# SM3320-BATT-EV.net
KiCad netlist of a schematic drawn in Altium Designer
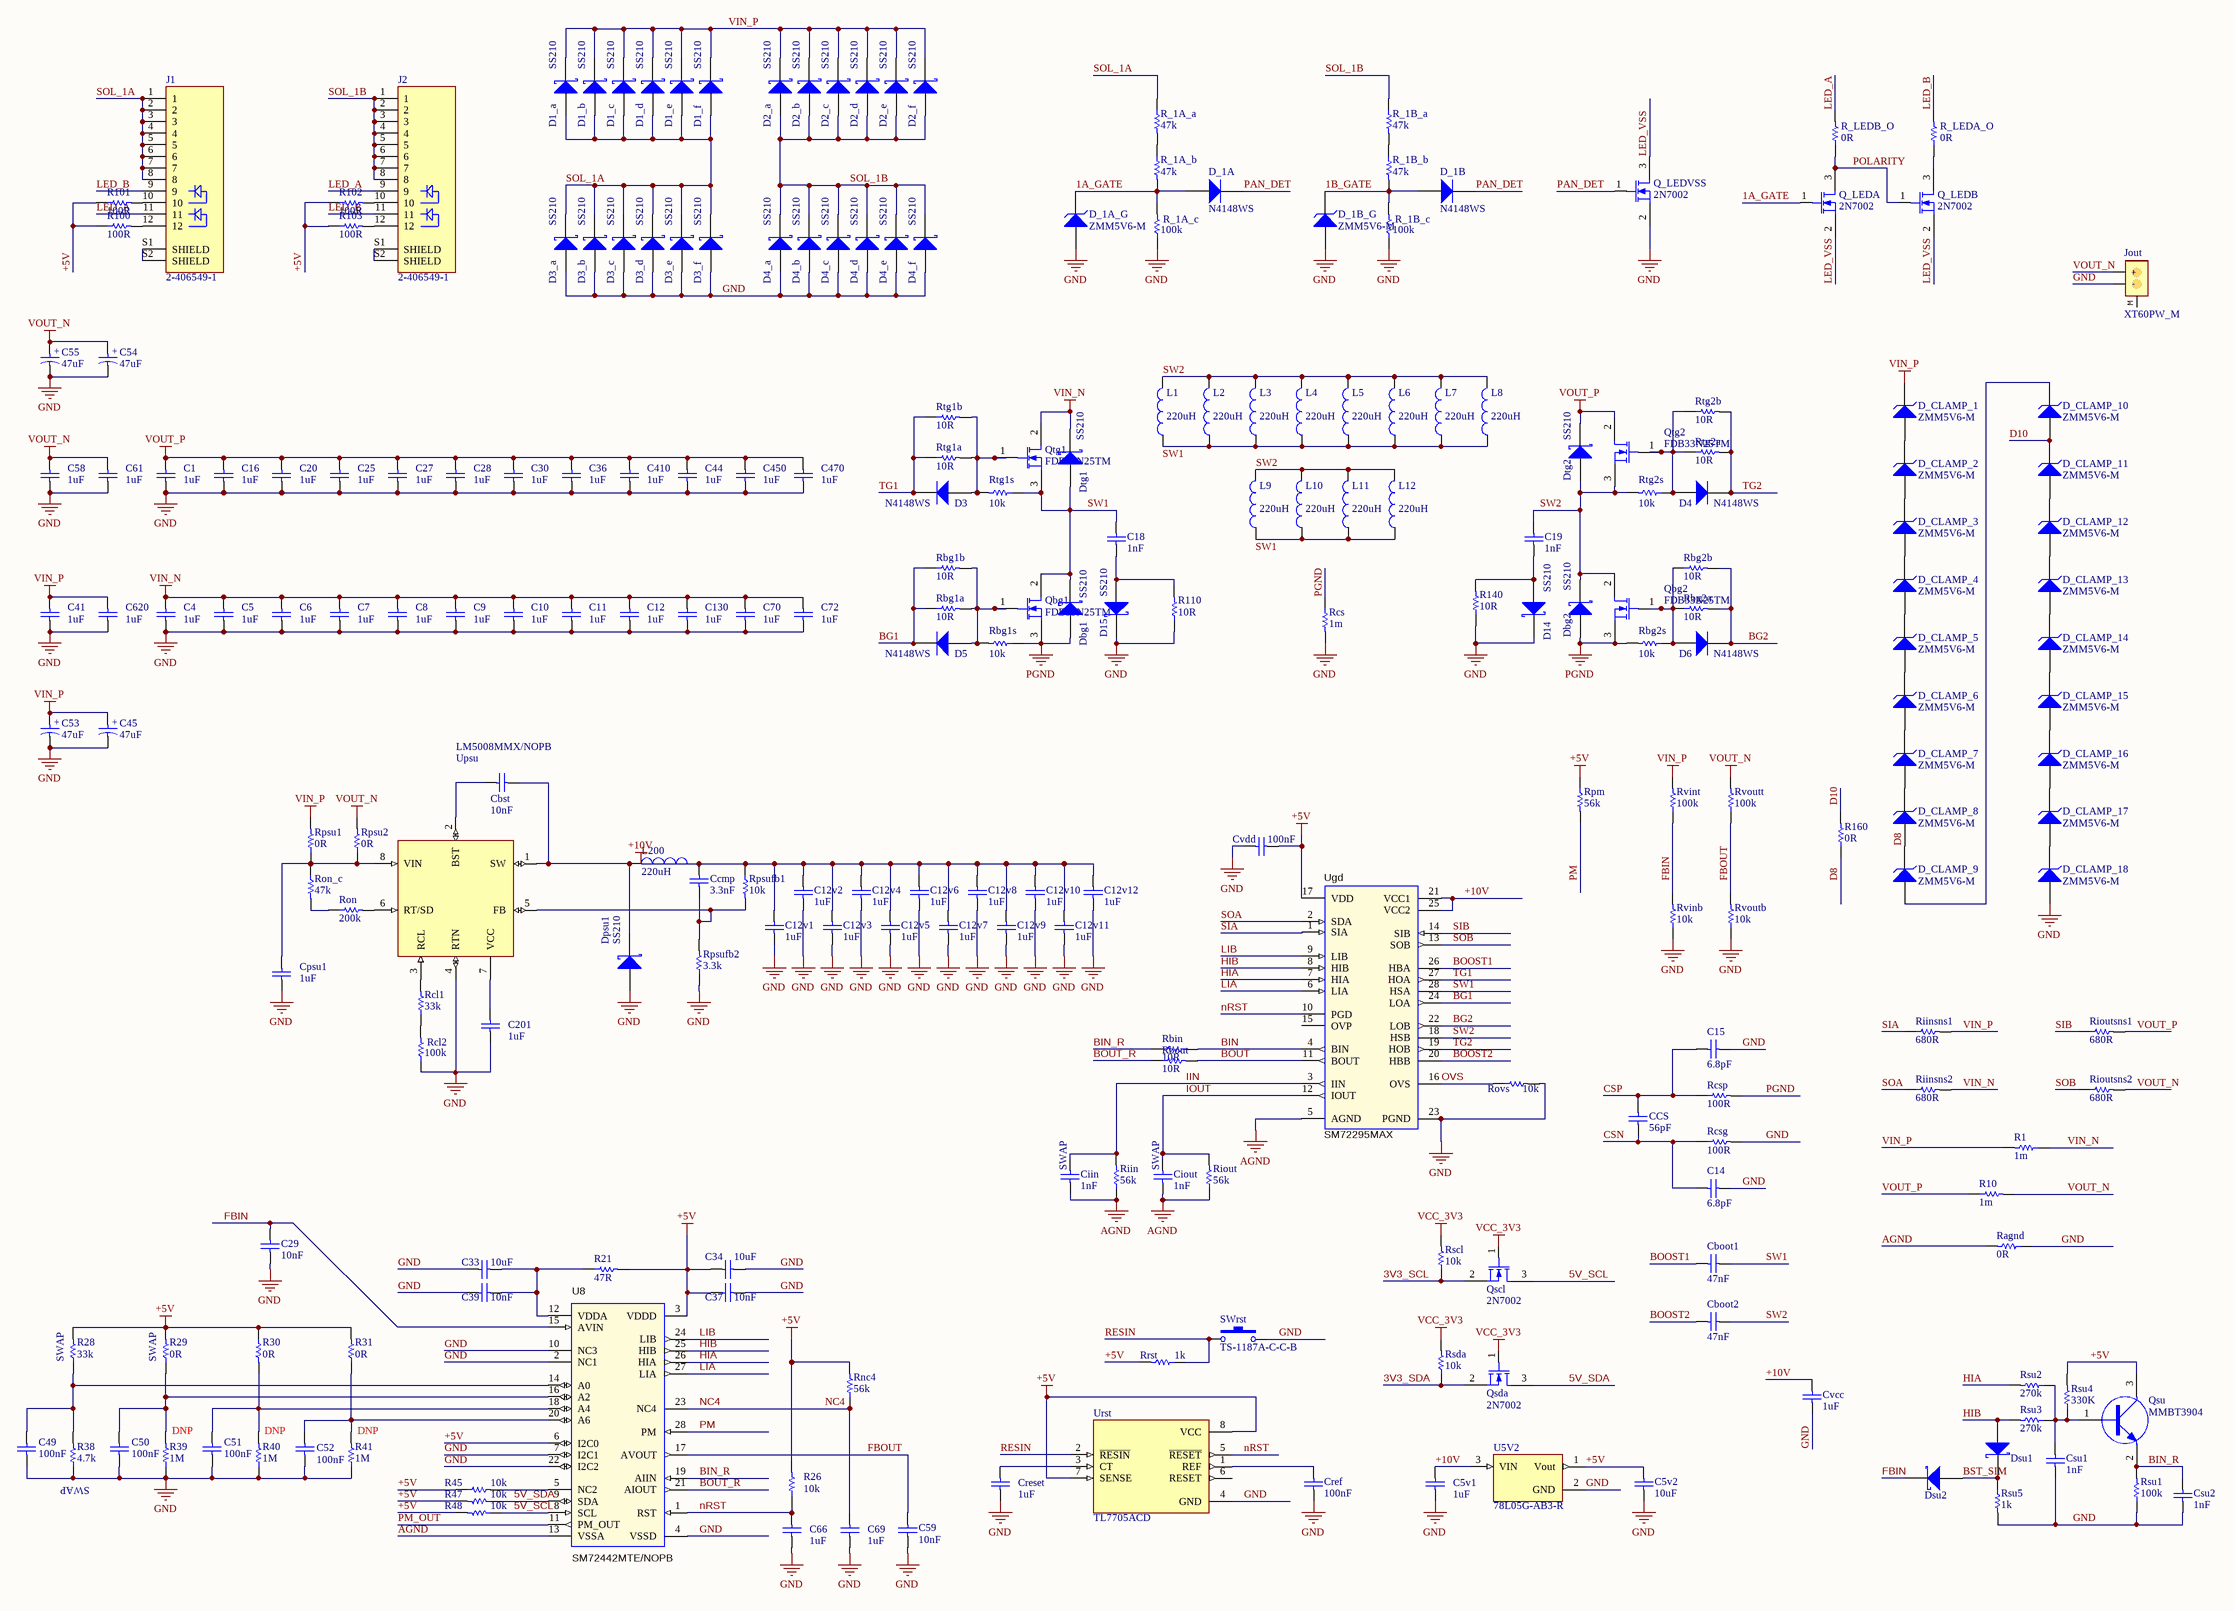
[diagram p0: SM3320-BATT-EV.SchDoc]

(export (version "E")
  (design (tool "Eeschema 10.0.6"))
  (components
    (comp (ref "C1")
      (value "1uF")
      (footprint "C_1206")
      (description "C - CAPACITOR - MLCC - 1uF - 100V - 1206 - X7R")
      (fields (field (name "LCSC PART #") "C91151") (field (name "Comment") "1206B105K101NT"))
      (libsource (lib "JLC_PCB") (part "1206B105K101NT"))
    )
    (comp (ref "C4")
      (value "1uF")
      (footprint "C_1206")
      (description "C - CAPACITOR - MLCC - 1uF - 100V - 1206 - X7R")
      (fields (field (name "LCSC PART #") "C91151") (field (name "Comment") "1206B105K101NT"))
      (libsource (lib "JLC_PCB") (part "1206B105K101NT"))
    )
    (comp (ref "C5")
      (value "1uF")
      (footprint "C_1206")
      (description "C - CAPACITOR - MLCC - 1uF - 100V - 1206 - X7R")
      (fields (field (name "LCSC PART #") "C91151") (field (name "Comment") "1206B105K101NT"))
      (libsource (lib "JLC_PCB") (part "1206B105K101NT"))
    )
    (comp (ref "C5v1")
      (value "1uF")
      (footprint "C_0402")
      (description "C - CAPACITOR - MLCC - 1uF - 25V - 0402")
      (fields (field (name "LCSC PART #") "C52923") (field (name "Comment") "CL05A105KA5NQNC"))
      (libsource (lib "JLC_PCB") (part "CL05A105KA5NQNC"))
    )
    (comp (ref "C5v2")
      (value "10uF")
      (footprint "C_0402")
      (description "C - CAPACITOR - MLCC - 10uF - 6.3V - 0402")
      (fields (field (name "LCSC PART #") "C15525") (field (name "Comment") "CL05A106MQ5NUNC"))
      (libsource (lib "JLC_PCB") (part "CL05A106MQ5NUNC"))
    )
    (comp (ref "C6")
      (value "1uF")
      (footprint "C_1206")
      (description "C - CAPACITOR - MLCC - 1uF - 100V - 1206 - X7R")
      (fields (field (name "LCSC PART #") "C91151") (field (name "Comment") "1206B105K101NT"))
      (libsource (lib "JLC_PCB") (part "1206B105K101NT"))
    )
    (comp (ref "C7")
      (value "1uF")
      (footprint "C_1206")
      (description "C - CAPACITOR - MLCC - 1uF - 100V - 1206 - X7R")
      (fields (field (name "LCSC PART #") "C91151") (field (name "Comment") "1206B105K101NT"))
      (libsource (lib "JLC_PCB") (part "1206B105K101NT"))
    )
    (comp (ref "C8")
      (value "1uF")
      (footprint "C_1206")
      (description "C - CAPACITOR - MLCC - 1uF - 100V - 1206 - X7R")
      (fields (field (name "LCSC PART #") "C91151") (field (name "Comment") "1206B105K101NT"))
      (libsource (lib "JLC_PCB") (part "1206B105K101NT"))
    )
    (comp (ref "C9")
      (value "1uF")
      (footprint "C_1206")
      (description "C - CAPACITOR - MLCC - 1uF - 100V - 1206 - X7R")
      (fields (field (name "LCSC PART #") "C91151") (field (name "Comment") "1206B105K101NT"))
      (libsource (lib "JLC_PCB") (part "1206B105K101NT"))
    )
    (comp (ref "C10")
      (value "1uF")
      (footprint "C_1206")
      (description "C - CAPACITOR - MLCC - 1uF - 100V - 1206 - X7R")
      (fields (field (name "LCSC PART #") "C91151") (field (name "Comment") "1206B105K101NT"))
      (libsource (lib "JLC_PCB") (part "1206B105K101NT"))
    )
    (comp (ref "C11")
      (value "1uF")
      (footprint "C_1206")
      (description "C - CAPACITOR - MLCC - 1uF - 100V - 1206 - X7R")
      (fields (field (name "LCSC PART #") "C91151") (field (name "Comment") "1206B105K101NT"))
      (libsource (lib "JLC_PCB") (part "1206B105K101NT"))
    )
    (comp (ref "C12")
      (value "1uF")
      (footprint "C_1206")
      (description "C - CAPACITOR - MLCC - 1uF - 100V - 1206 - X7R")
      (fields (field (name "LCSC PART #") "C91151") (field (name "Comment") "1206B105K101NT"))
      (libsource (lib "JLC_PCB") (part "1206B105K101NT"))
    )
    (comp (ref "C12v1")
      (value "1uF")
      (footprint "C_0402")
      (description "C - CAPACITOR - MLCC - 1uF - 25V - 0402")
      (fields (field (name "LCSC PART #") "C52923") (field (name "Comment") "CL05A105KA5NQNC"))
      (libsource (lib "JLC_PCB") (part "CL05A105KA5NQNC"))
    )
    (comp (ref "C12v2")
      (value "1uF")
      (footprint "C_0402")
      (description "C - CAPACITOR - MLCC - 1uF - 25V - 0402")
      (fields (field (name "LCSC PART #") "C52923") (field (name "Comment") "CL05A105KA5NQNC"))
      (libsource (lib "JLC_PCB") (part "CL05A105KA5NQNC"))
    )
    (comp (ref "C12v3")
      (value "1uF")
      (footprint "C_0402")
      (description "C - CAPACITOR - MLCC - 1uF - 25V - 0402")
      (fields (field (name "LCSC PART #") "C52923") (field (name "Comment") "CL05A105KA5NQNC"))
      (libsource (lib "JLC_PCB") (part "CL05A105KA5NQNC"))
    )
    (comp (ref "C12v4")
      (value "1uF")
      (footprint "C_0402")
      (description "C - CAPACITOR - MLCC - 1uF - 25V - 0402")
      (fields (field (name "LCSC PART #") "C52923") (field (name "Comment") "CL05A105KA5NQNC"))
      (libsource (lib "JLC_PCB") (part "CL05A105KA5NQNC"))
    )
    (comp (ref "C12v5")
      (value "1uF")
      (footprint "C_0402")
      (description "C - CAPACITOR - MLCC - 1uF - 25V - 0402")
      (fields (field (name "LCSC PART #") "C52923") (field (name "Comment") "CL05A105KA5NQNC"))
      (libsource (lib "JLC_PCB") (part "CL05A105KA5NQNC"))
    )
    (comp (ref "C12v6")
      (value "1uF")
      (footprint "C_0402")
      (description "C - CAPACITOR - MLCC - 1uF - 25V - 0402")
      (fields (field (name "LCSC PART #") "C52923") (field (name "Comment") "CL05A105KA5NQNC"))
      (libsource (lib "JLC_PCB") (part "CL05A105KA5NQNC"))
    )
    (comp (ref "C12v7")
      (value "1uF")
      (footprint "C_0402")
      (description "C - CAPACITOR - MLCC - 1uF - 25V - 0402")
      (fields (field (name "LCSC PART #") "C52923") (field (name "Comment") "CL05A105KA5NQNC"))
      (libsource (lib "JLC_PCB") (part "CL05A105KA5NQNC"))
    )
    (comp (ref "C12v8")
      (value "1uF")
      (footprint "C_0402")
      (description "C - CAPACITOR - MLCC - 1uF - 25V - 0402")
      (fields (field (name "LCSC PART #") "C52923") (field (name "Comment") "CL05A105KA5NQNC"))
      (libsource (lib "JLC_PCB") (part "CL05A105KA5NQNC"))
    )
    (comp (ref "C12v9")
      (value "1uF")
      (footprint "C_0402")
      (description "C - CAPACITOR - MLCC - 1uF - 25V - 0402")
      (fields (field (name "LCSC PART #") "C52923") (field (name "Comment") "CL05A105KA5NQNC"))
      (libsource (lib "JLC_PCB") (part "CL05A105KA5NQNC"))
    )
    (comp (ref "C12v10")
      (value "1uF")
      (footprint "C_0402")
      (description "C - CAPACITOR - MLCC - 1uF - 25V - 0402")
      (fields (field (name "LCSC PART #") "C52923") (field (name "Comment") "CL05A105KA5NQNC"))
      (libsource (lib "JLC_PCB") (part "CL05A105KA5NQNC"))
    )
    (comp (ref "C12v11")
      (value "1uF")
      (footprint "C_0402")
      (description "C - CAPACITOR - MLCC - 1uF - 25V - 0402")
      (fields (field (name "LCSC PART #") "C52923") (field (name "Comment") "CL05A105KA5NQNC"))
      (libsource (lib "JLC_PCB") (part "CL05A105KA5NQNC"))
    )
    (comp (ref "C12v12")
      (value "1uF")
      (footprint "C_0402")
      (description "C - CAPACITOR - MLCC - 1uF - 25V - 0402")
      (fields (field (name "LCSC PART #") "C52923") (field (name "Comment") "CL05A105KA5NQNC"))
      (libsource (lib "JLC_PCB") (part "CL05A105KA5NQNC"))
    )
    (comp (ref "C14")
      (value "6.8pF")
      (footprint "C_0402")
      (description "C - CAPACITOR - MLCC - 6.8pF - 50V - 0402")
      (fields (field (name "LCSC PART #") "C1576") (field (name "Comment") "0402CG6R8C500NT"))
      (libsource (lib "JLC_PCB") (part "0402CG6R8C500NT"))
    )
    (comp (ref "C15")
      (value "6.8pF")
      (footprint "C_0402")
      (description "C - CAPACITOR - MLCC - 6.8pF - 50V - 0402")
      (fields (field (name "LCSC PART #") "C1576") (field (name "Comment") "0402CG6R8C500NT"))
      (libsource (lib "JLC_PCB") (part "0402CG6R8C500NT"))
    )
    (comp (ref "C16")
      (value "1uF")
      (footprint "C_1206")
      (description "C - CAPACITOR - MLCC - 1uF - 100V - 1206 - X7R")
      (fields (field (name "LCSC PART #") "C91151") (field (name "Comment") "1206B105K101NT"))
      (libsource (lib "JLC_PCB") (part "1206B105K101NT"))
    )
    (comp (ref "C18")
      (value "1nF")
      (footprint "C_1206")
      (description "C - CAPACITOR - MLCC - 1nF - 2000V - 1206 - X7R")
      (fields (field (name "LCSC PART #") "C9196") (field (name "Comment") "1206B102K202NT"))
      (libsource (lib "JLC_PCB") (part "1206B102K202NT"))
    )
    (comp (ref "C19")
      (value "1nF")
      (footprint "C_1206")
      (description "C - CAPACITOR - MLCC - 1nF - 2000V - 1206 - X7R")
      (fields (field (name "LCSC PART #") "C9196") (field (name "Comment") "1206B102K202NT"))
      (libsource (lib "JLC_PCB") (part "1206B102K202NT"))
    )
    (comp (ref "C20")
      (value "1uF")
      (footprint "C_1206")
      (description "C - CAPACITOR - MLCC - 1uF - 100V - 1206 - X7R")
      (fields (field (name "LCSC PART #") "C91151") (field (name "Comment") "1206B105K101NT"))
      (libsource (lib "JLC_PCB") (part "1206B105K101NT"))
    )
    (comp (ref "C25")
      (value "1uF")
      (footprint "C_1206")
      (description "C - CAPACITOR - MLCC - 1uF - 100V - 1206 - X7R")
      (fields (field (name "LCSC PART #") "C91151") (field (name "Comment") "1206B105K101NT"))
      (libsource (lib "JLC_PCB") (part "1206B105K101NT"))
    )
    (comp (ref "C27")
      (value "1uF")
      (footprint "C_1206")
      (description "C - CAPACITOR - MLCC - 1uF - 100V - 1206 - X7R")
      (fields (field (name "LCSC PART #") "C91151") (field (name "Comment") "1206B105K101NT"))
      (libsource (lib "JLC_PCB") (part "1206B105K101NT"))
    )
    (comp (ref "C28")
      (value "1uF")
      (footprint "C_1206")
      (description "C - CAPACITOR - MLCC - 1uF - 100V - 1206 - X7R")
      (fields (field (name "LCSC PART #") "C91151") (field (name "Comment") "1206B105K101NT"))
      (libsource (lib "JLC_PCB") (part "1206B105K101NT"))
    )
    (comp (ref "C29")
      (value "10nF")
      (footprint "C_0402")
      (description "C - CAPACITOR - MLCC - 10nF - 50V - 0402")
      (fields (field (name "LCSC PART #") "C15195") (field (name "Comment") "CL05B103KB5NNNC"))
      (libsource (lib "JLC_PCB") (part "CL05B103KB5NNNC"))
    )
    (comp (ref "C30")
      (value "1uF")
      (footprint "C_1206")
      (description "C - CAPACITOR - MLCC - 1uF - 100V - 1206 - X7R")
      (fields (field (name "LCSC PART #") "C91151") (field (name "Comment") "1206B105K101NT"))
      (libsource (lib "JLC_PCB") (part "1206B105K101NT"))
    )
    (comp (ref "C33")
      (value "10uF")
      (footprint "C_0402")
      (description "C - CAPACITOR - MLCC - 10uF - 6.3V - 0402")
      (fields (field (name "LCSC PART #") "C15525") (field (name "Comment") "CL05A106MQ5NUNC"))
      (libsource (lib "JLC_PCB") (part "CL05A106MQ5NUNC"))
    )
    (comp (ref "C34")
      (value "10uF")
      (footprint "C_0402")
      (description "C - CAPACITOR - MLCC - 10uF - 6.3V - 0402")
      (fields (field (name "LCSC PART #") "C15525") (field (name "Comment") "CL05A106MQ5NUNC"))
      (libsource (lib "JLC_PCB") (part "CL05A106MQ5NUNC"))
    )
    (comp (ref "C36")
      (value "1uF")
      (footprint "C_1206")
      (description "C - CAPACITOR - MLCC - 1uF - 100V - 1206 - X7R")
      (fields (field (name "LCSC PART #") "C91151") (field (name "Comment") "1206B105K101NT"))
      (libsource (lib "JLC_PCB") (part "1206B105K101NT"))
    )
    (comp (ref "C37")
      (value "10nF")
      (footprint "C_0402")
      (description "C - CAPACITOR - MLCC - 10nF - 50V - 0402")
      (fields (field (name "LCSC PART #") "C15195") (field (name "Comment") "CL05B103KB5NNNC"))
      (libsource (lib "JLC_PCB") (part "CL05B103KB5NNNC"))
    )
    (comp (ref "C39")
      (value "10nF")
      (footprint "C_0402")
      (description "C - CAPACITOR - MLCC - 10nF - 50V - 0402")
      (fields (field (name "LCSC PART #") "C15195") (field (name "Comment") "CL05B103KB5NNNC"))
      (libsource (lib "JLC_PCB") (part "CL05B103KB5NNNC"))
    )
    (comp (ref "C41")
      (value "1uF")
      (footprint "C_1206")
      (description "C - CAPACITOR - MLCC - 1uF - 100V - 1206 - X7R")
      (fields (field (name "LCSC PART #") "C91151") (field (name "Comment") "1206B105K101NT"))
      (libsource (lib "JLC_PCB") (part "1206B105K101NT"))
    )
    (comp (ref "C44")
      (value "1uF")
      (footprint "C_1206")
      (description "C - CAPACITOR - MLCC - 1uF - 100V - 1206 - X7R")
      (fields (field (name "LCSC PART #") "C91151") (field (name "Comment") "1206B105K101NT"))
      (libsource (lib "JLC_PCB") (part "1206B105K101NT"))
    )
    (comp (ref "C45")
      (value "47uF")
      (footprint "C_CAN_1010")
      (description "C - CAPACITOR - ELECTROLYTIC - 47uF - 100V")
      (fields (field (name "LCSC PART #") "C164068") (field (name "Comment") "VZH470M2ATR-1010"))
      (libsource (lib "JLC_PCB") (part "VZH470M2ATR-1010"))
    )
    (comp (ref "C49")
      (value "100nF")
      (footprint "C_0402")
      (description "C - CAPACITOR - MLCC - 100nF - 16V - 0402")
      (fields (field (name "LCSC PART #") "C1525") (field (name "Comment") "CL05B104KO5NNNC"))
      (libsource (lib "JLC_PCB") (part "CL05B104KO5NNNC"))
    )
    (comp (ref "C50")
      (value "100nF")
      (footprint "C_0402")
      (description "C - CAPACITOR - MLCC - 100nF - 16V - 0402")
      (fields (field (name "LCSC PART #") "C1525") (field (name "Comment") "CL05B104KO5NNNC"))
      (libsource (lib "JLC_PCB") (part "CL05B104KO5NNNC"))
    )
    (comp (ref "C51")
      (value "100nF")
      (footprint "C_0402")
      (description "C - CAPACITOR - MLCC - 100nF - 16V - 0402")
      (fields (field (name "LCSC PART #") "C1525") (field (name "Comment") "CL05B104KO5NNNC"))
      (libsource (lib "JLC_PCB") (part "CL05B104KO5NNNC"))
    )
    (comp (ref "C52")
      (value "100nF")
      (footprint "C_0402")
      (description "C - CAPACITOR - MLCC - 100nF - 16V - 0402")
      (fields (field (name "LCSC PART #") "C1525") (field (name "Comment") "CL05B104KO5NNNC"))
      (libsource (lib "JLC_PCB") (part "CL05B104KO5NNNC"))
    )
    (comp (ref "C53")
      (value "47uF")
      (footprint "C_CAN_1010")
      (description "C - CAPACITOR - ELECTROLYTIC - 47uF - 100V")
      (fields (field (name "LCSC PART #") "C164068") (field (name "Comment") "VZH470M2ATR-1010"))
      (libsource (lib "JLC_PCB") (part "VZH470M2ATR-1010"))
    )
    (comp (ref "C54")
      (value "47uF")
      (footprint "C_CAN_1010")
      (description "C - CAPACITOR - ELECTROLYTIC - 47uF - 100V")
      (fields (field (name "LCSC PART #") "C164068") (field (name "Comment") "VZH470M2ATR-1010"))
      (libsource (lib "JLC_PCB") (part "VZH470M2ATR-1010"))
    )
    (comp (ref "C55")
      (value "47uF")
      (footprint "C_CAN_1010")
      (description "C - CAPACITOR - ELECTROLYTIC - 47uF - 100V")
      (fields (field (name "LCSC PART #") "C164068") (field (name "Comment") "VZH470M2ATR-1010"))
      (libsource (lib "JLC_PCB") (part "VZH470M2ATR-1010"))
    )
    (comp (ref "C58")
      (value "1uF")
      (footprint "C_1206")
      (description "C - CAPACITOR - MLCC - 1uF - 100V - 1206 - X7R")
      (fields (field (name "LCSC PART #") "C91151") (field (name "Comment") "1206B105K101NT"))
      (libsource (lib "JLC_PCB") (part "1206B105K101NT"))
    )
    (comp (ref "C59")
      (value "10nF")
      (footprint "C_0402")
      (description "C - CAPACITOR - MLCC - 10nF - 50V - 0402")
      (fields (field (name "LCSC PART #") "C15195") (field (name "Comment") "CL05B103KB5NNNC"))
      (libsource (lib "JLC_PCB") (part "CL05B103KB5NNNC"))
    )
    (comp (ref "C61")
      (value "1uF")
      (footprint "C_1206")
      (description "C - CAPACITOR - MLCC - 1uF - 100V - 1206 - X7R")
      (fields (field (name "LCSC PART #") "C91151") (field (name "Comment") "1206B105K101NT"))
      (libsource (lib "JLC_PCB") (part "1206B105K101NT"))
    )
    (comp (ref "C66")
      (value "1uF")
      (footprint "C_0402")
      (description "C - CAPACITOR - MLCC - 1uF - 25V - 0402")
      (fields (field (name "LCSC PART #") "C52923") (field (name "Comment") "CL05A105KA5NQNC"))
      (libsource (lib "JLC_PCB") (part "CL05A105KA5NQNC"))
    )
    (comp (ref "C69")
      (value "1uF")
      (footprint "C_0402")
      (description "C - CAPACITOR - MLCC - 1uF - 25V - 0402")
      (fields (field (name "LCSC PART #") "C52923") (field (name "Comment") "CL05A105KA5NQNC"))
      (libsource (lib "JLC_PCB") (part "CL05A105KA5NQNC"))
    )
    (comp (ref "C70")
      (value "1uF")
      (footprint "C_1206")
      (description "C - CAPACITOR - MLCC - 1uF - 100V - 1206 - X7R")
      (fields (field (name "LCSC PART #") "C91151") (field (name "Comment") "1206B105K101NT"))
      (libsource (lib "JLC_PCB") (part "1206B105K101NT"))
    )
    (comp (ref "C72")
      (value "1uF")
      (footprint "C_1206")
      (description "C - CAPACITOR - MLCC - 1uF - 100V - 1206 - X7R")
      (fields (field (name "LCSC PART #") "C91151") (field (name "Comment") "1206B105K101NT"))
      (libsource (lib "JLC_PCB") (part "1206B105K101NT"))
    )
    (comp (ref "C130")
      (value "1uF")
      (footprint "C_1206")
      (description "C - CAPACITOR - MLCC - 1uF - 100V - 1206 - X7R")
      (fields (field (name "LCSC PART #") "C91151") (field (name "Comment") "1206B105K101NT"))
      (libsource (lib "JLC_PCB") (part "1206B105K101NT"))
    )
    (comp (ref "C201")
      (value "1uF")
      (footprint "C_0402")
      (description "C - CAPACITOR - MLCC - 1uF - 25V - 0402")
      (fields (field (name "LCSC PART #") "C52923") (field (name "Comment") "CL05A105KA5NQNC"))
      (libsource (lib "JLC_PCB") (part "CL05A105KA5NQNC"))
    )
    (comp (ref "C410")
      (value "1uF")
      (footprint "C_1206")
      (description "C - CAPACITOR - MLCC - 1uF - 100V - 1206 - X7R")
      (fields (field (name "LCSC PART #") "C91151") (field (name "Comment") "1206B105K101NT"))
      (libsource (lib "JLC_PCB") (part "1206B105K101NT"))
    )
    (comp (ref "C450")
      (value "1uF")
      (footprint "C_1206")
      (description "C - CAPACITOR - MLCC - 1uF - 100V - 1206 - X7R")
      (fields (field (name "LCSC PART #") "C91151") (field (name "Comment") "1206B105K101NT"))
      (libsource (lib "JLC_PCB") (part "1206B105K101NT"))
    )
    (comp (ref "C470")
      (value "1uF")
      (footprint "C_1206")
      (description "C - CAPACITOR - MLCC - 1uF - 100V - 1206 - X7R")
      (fields (field (name "LCSC PART #") "C91151") (field (name "Comment") "1206B105K101NT"))
      (libsource (lib "JLC_PCB") (part "1206B105K101NT"))
    )
    (comp (ref "C620")
      (value "1uF")
      (footprint "C_1206")
      (description "C - CAPACITOR - MLCC - 1uF - 100V - 1206 - X7R")
      (fields (field (name "LCSC PART #") "C91151") (field (name "Comment") "1206B105K101NT"))
      (libsource (lib "JLC_PCB") (part "1206B105K101NT"))
    )
    (comp (ref "Cboot1")
      (value "47nF")
      (footprint "C_0603")
      (description "C - CAPACITOR - MLCC - 470nF - 25V - 0603")
      (fields (field (name "LCSC PART #") "C1623") (field (name "Comment") "CL10B474KA8NNNC"))
      (libsource (lib "JLC_PCB") (part "CL10B474KA8NNNC"))
    )
    (comp (ref "Cboot2")
      (value "47nF")
      (footprint "C_0603")
      (description "C - CAPACITOR - MLCC - 470nF - 25V - 0603")
      (fields (field (name "LCSC PART #") "C1623") (field (name "Comment") "CL10B474KA8NNNC"))
      (libsource (lib "JLC_PCB") (part "CL10B474KA8NNNC"))
    )
    (comp (ref "Cbst")
      (value "10nF")
      (footprint "C_0402")
      (description "C - CAPACITOR - MLCC - 10nF - 50V - 0402")
      (fields (field (name "LCSC PART #") "C15195") (field (name "Comment") "CL05B103KB5NNNC"))
      (libsource (lib "JLC_PCB") (part "CL05B103KB5NNNC"))
    )
    (comp (ref "Ccmp")
      (value "3.3nF")
      (footprint "C_0402")
      (description "C - CAPACITOR - MLCC - 3.3nF - 50V - 0402")
      (fields (field (name "LCSC PART #") "C26404") (field (name "Comment") "CL05B332KB5NNNC"))
      (libsource (lib "JLC_PCB") (part "CL05B332KB5NNNC"))
    )
    (comp (ref "CCS")
      (value "56pF")
      (footprint "C_0402")
      (description "C - CAPACITOR - MLCC - 56pF - 50V -  0402")
      (fields (field (name "LCSC PART #") "C1572") (field (name "Comment") "0402CG560J500NT"))
      (libsource (lib "JLC_PCB") (part "0402CG560J500NT"))
    )
    (comp (ref "Ciin")
      (value "1nF")
      (footprint "C_0402")
      (description "C - CAPACITOR - MLCC - 1nF - 50V - 0402")
      (fields (field (name "LCSC PART #") "C1523") (field (name "Comment") "0402B102K500NT"))
      (libsource (lib "JLC_PCB") (part "0402B102K500NT"))
    )
    (comp (ref "Ciout")
      (value "1nF")
      (footprint "C_0402")
      (description "C - CAPACITOR - MLCC - 1nF - 50V - 0402")
      (fields (field (name "LCSC PART #") "C1523") (field (name "Comment") "0402B102K500NT"))
      (libsource (lib "JLC_PCB") (part "0402B102K500NT"))
    )
    (comp (ref "Cpsu1")
      (value "1uF")
      (footprint "C_1206")
      (description "C - CAPACITOR - MLCC - 1uF - 100V - 1206 - X7R")
      (fields (field (name "LCSC PART #") "C91151") (field (name "Comment") "1206B105K101NT"))
      (libsource (lib "JLC_PCB") (part "1206B105K101NT"))
    )
    (comp (ref "Cref")
      (value "100nF")
      (footprint "C_0402")
      (description "C - CAPACITOR - MLCC - 100nF - 16V - 0402")
      (fields (field (name "LCSC PART #") "C1525") (field (name "Comment") "CL05B104KO5NNNC"))
      (libsource (lib "JLC_PCB") (part "CL05B104KO5NNNC"))
    )
    (comp (ref "Creset")
      (value "1uF")
      (footprint "C_0402")
      (description "C - CAPACITOR - MLCC - 1uF - 25V - 0402")
      (fields (field (name "LCSC PART #") "C52923") (field (name "Comment") "CL05A105KA5NQNC"))
      (libsource (lib "JLC_PCB") (part "CL05A105KA5NQNC"))
    )
    (comp (ref "Csu1")
      (value "1nF")
      (footprint "C_0402")
      (description "C - CAPACITOR - MLCC - 1nF - 50V - 0402")
      (fields (field (name "LCSC PART #") "C1523") (field (name "Comment") "0402B102K500NT"))
      (libsource (lib "JLC_PCB") (part "0402B102K500NT"))
    )
    (comp (ref "Csu2")
      (value "1nF")
      (footprint "C_0402")
      (description "C - CAPACITOR - MLCC - 1nF - 50V - 0402")
      (fields (field (name "LCSC PART #") "C1523") (field (name "Comment") "0402B102K500NT"))
      (libsource (lib "JLC_PCB") (part "0402B102K500NT"))
    )
    (comp (ref "Cvcc")
      (value "1uF")
      (footprint "C_0402")
      (description "C - CAPACITOR - MLCC - 1uF - 25V - 0402")
      (fields (field (name "LCSC PART #") "C52923") (field (name "Comment") "CL05A105KA5NQNC"))
      (libsource (lib "JLC_PCB") (part "CL05A105KA5NQNC"))
    )
    (comp (ref "Cvdd")
      (value "100nF")
      (footprint "C_0402")
      (description "C - CAPACITOR - MLCC - 100nF - 16V - 0402")
      (fields (field (name "LCSC PART #") "C1525") (field (name "Comment") "CL05B104KO5NNNC"))
      (libsource (lib "JLC_PCB") (part "CL05B104KO5NNNC"))
    )
    (comp (ref "D1_a")
      (value "SS210")
      (footprint "DO-214AC")
      (description "D - DIODE - SCHOTTKY - 100V - 2A")
      (fields (field (name "LCSC PART #") "C14996"))
      (libsource (lib "JLC_PCB") (part "SS210"))
    )
    (comp (ref "D1_b")
      (value "SS210")
      (footprint "DO-214AC")
      (description "D - DIODE - SCHOTTKY - 100V - 2A")
      (fields (field (name "LCSC PART #") "C14996"))
      (libsource (lib "JLC_PCB") (part "SS210"))
    )
    (comp (ref "D1_c")
      (value "SS210")
      (footprint "DO-214AC")
      (description "D - DIODE - SCHOTTKY - 100V - 2A")
      (fields (field (name "LCSC PART #") "C14996"))
      (libsource (lib "JLC_PCB") (part "SS210"))
    )
    (comp (ref "D1_d")
      (value "SS210")
      (footprint "DO-214AC")
      (description "D - DIODE - SCHOTTKY - 100V - 2A")
      (fields (field (name "LCSC PART #") "C14996"))
      (libsource (lib "JLC_PCB") (part "SS210"))
    )
    (comp (ref "D1_e")
      (value "SS210")
      (footprint "DO-214AC")
      (description "D - DIODE - SCHOTTKY - 100V - 2A")
      (fields (field (name "LCSC PART #") "C14996"))
      (libsource (lib "JLC_PCB") (part "SS210"))
    )
    (comp (ref "D1_f")
      (value "SS210")
      (footprint "DO-214AC")
      (description "D - DIODE - SCHOTTKY - 100V - 2A")
      (fields (field (name "LCSC PART #") "C14996"))
      (libsource (lib "JLC_PCB") (part "SS210"))
    )
    (comp (ref "D2_a")
      (value "SS210")
      (footprint "DO-214AC")
      (description "D - DIODE - SCHOTTKY - 100V - 2A")
      (fields (field (name "LCSC PART #") "C14996"))
      (libsource (lib "JLC_PCB") (part "SS210"))
    )
    (comp (ref "D2_b")
      (value "SS210")
      (footprint "DO-214AC")
      (description "D - DIODE - SCHOTTKY - 100V - 2A")
      (fields (field (name "LCSC PART #") "C14996"))
      (libsource (lib "JLC_PCB") (part "SS210"))
    )
    (comp (ref "D2_c")
      (value "SS210")
      (footprint "DO-214AC")
      (description "D - DIODE - SCHOTTKY - 100V - 2A")
      (fields (field (name "LCSC PART #") "C14996"))
      (libsource (lib "JLC_PCB") (part "SS210"))
    )
    (comp (ref "D2_d")
      (value "SS210")
      (footprint "DO-214AC")
      (description "D - DIODE - SCHOTTKY - 100V - 2A")
      (fields (field (name "LCSC PART #") "C14996"))
      (libsource (lib "JLC_PCB") (part "SS210"))
    )
    (comp (ref "D2_e")
      (value "SS210")
      (footprint "DO-214AC")
      (description "D - DIODE - SCHOTTKY - 100V - 2A")
      (fields (field (name "LCSC PART #") "C14996"))
      (libsource (lib "JLC_PCB") (part "SS210"))
    )
    (comp (ref "D2_f")
      (value "SS210")
      (footprint "DO-214AC")
      (description "D - DIODE - SCHOTTKY - 100V - 2A")
      (fields (field (name "LCSC PART #") "C14996"))
      (libsource (lib "JLC_PCB") (part "SS210"))
    )
    (comp (ref "D3")
      (value "N4148WS")
      (footprint "SOD-323")
      (description "D - DIODE - FAST TRR - 100V - 150mA - 4ns")
      (fields (field (name "LCSC PART #") "C2128"))
      (libsource (lib "JLC_PCB") (part "N4148WS"))
    )
    (comp (ref "D3_a")
      (value "SS210")
      (footprint "DO-214AC")
      (description "D - DIODE - SCHOTTKY - 100V - 2A")
      (fields (field (name "LCSC PART #") "C14996"))
      (libsource (lib "JLC_PCB") (part "SS210"))
    )
    (comp (ref "D3_b")
      (value "SS210")
      (footprint "DO-214AC")
      (description "D - DIODE - SCHOTTKY - 100V - 2A")
      (fields (field (name "LCSC PART #") "C14996"))
      (libsource (lib "JLC_PCB") (part "SS210"))
    )
    (comp (ref "D3_c")
      (value "SS210")
      (footprint "DO-214AC")
      (description "D - DIODE - SCHOTTKY - 100V - 2A")
      (fields (field (name "LCSC PART #") "C14996"))
      (libsource (lib "JLC_PCB") (part "SS210"))
    )
    (comp (ref "D3_d")
      (value "SS210")
      (footprint "DO-214AC")
      (description "D - DIODE - SCHOTTKY - 100V - 2A")
      (fields (field (name "LCSC PART #") "C14996"))
      (libsource (lib "JLC_PCB") (part "SS210"))
    )
    (comp (ref "D3_e")
      (value "SS210")
      (footprint "DO-214AC")
      (description "D - DIODE - SCHOTTKY - 100V - 2A")
      (fields (field (name "LCSC PART #") "C14996"))
      (libsource (lib "JLC_PCB") (part "SS210"))
    )
    (comp (ref "D3_f")
      (value "SS210")
      (footprint "DO-214AC")
      (description "D - DIODE - SCHOTTKY - 100V - 2A")
      (fields (field (name "LCSC PART #") "C14996"))
      (libsource (lib "JLC_PCB") (part "SS210"))
    )
    (comp (ref "D4")
      (value "N4148WS")
      (footprint "SOD-323")
      (description "D - DIODE - FAST TRR - 100V - 150mA - 4ns")
      (fields (field (name "LCSC PART #") "C2128"))
      (libsource (lib "JLC_PCB") (part "N4148WS"))
    )
    (comp (ref "D4_a")
      (value "SS210")
      (footprint "DO-214AC")
      (description "D - DIODE - SCHOTTKY - 100V - 2A")
      (fields (field (name "LCSC PART #") "C14996"))
      (libsource (lib "JLC_PCB") (part "SS210"))
    )
    (comp (ref "D4_b")
      (value "SS210")
      (footprint "DO-214AC")
      (description "D - DIODE - SCHOTTKY - 100V - 2A")
      (fields (field (name "LCSC PART #") "C14996"))
      (libsource (lib "JLC_PCB") (part "SS210"))
    )
    (comp (ref "D4_c")
      (value "SS210")
      (footprint "DO-214AC")
      (description "D - DIODE - SCHOTTKY - 100V - 2A")
      (fields (field (name "LCSC PART #") "C14996"))
      (libsource (lib "JLC_PCB") (part "SS210"))
    )
    (comp (ref "D4_d")
      (value "SS210")
      (footprint "DO-214AC")
      (description "D - DIODE - SCHOTTKY - 100V - 2A")
      (fields (field (name "LCSC PART #") "C14996"))
      (libsource (lib "JLC_PCB") (part "SS210"))
    )
    (comp (ref "D4_e")
      (value "SS210")
      (footprint "DO-214AC")
      (description "D - DIODE - SCHOTTKY - 100V - 2A")
      (fields (field (name "LCSC PART #") "C14996"))
      (libsource (lib "JLC_PCB") (part "SS210"))
    )
    (comp (ref "D4_f")
      (value "SS210")
      (footprint "DO-214AC")
      (description "D - DIODE - SCHOTTKY - 100V - 2A")
      (fields (field (name "LCSC PART #") "C14996"))
      (libsource (lib "JLC_PCB") (part "SS210"))
    )
    (comp (ref "D5")
      (value "N4148WS")
      (footprint "SOD-323")
      (description "D - DIODE - FAST TRR - 100V - 150mA - 4ns")
      (fields (field (name "LCSC PART #") "C2128"))
      (libsource (lib "JLC_PCB") (part "N4148WS"))
    )
    (comp (ref "D6")
      (value "N4148WS")
      (footprint "SOD-323")
      (description "D - DIODE - FAST TRR - 100V - 150mA - 4ns")
      (fields (field (name "LCSC PART #") "C2128"))
      (libsource (lib "JLC_PCB") (part "N4148WS"))
    )
    (comp (ref "D14")
      (value "SS210")
      (footprint "DO-214AC")
      (description "D - DIODE - SCHOTTKY - 100V - 2A")
      (fields (field (name "LCSC PART #") "C14996"))
      (libsource (lib "JLC_PCB") (part "SS210"))
    )
    (comp (ref "D15")
      (value "SS210")
      (footprint "DO-214AC")
      (description "D - DIODE - SCHOTTKY - 100V - 2A")
      (fields (field (name "LCSC PART #") "C14996"))
      (libsource (lib "JLC_PCB") (part "SS210"))
    )
    (comp (ref "Dbg1")
      (value "SS210")
      (footprint "DO-214AC")
      (description "D - DIODE - SCHOTTKY - 100V - 2A")
      (fields (field (name "LCSC PART #") "C14996"))
      (libsource (lib "JLC_PCB") (part "SS210"))
    )
    (comp (ref "Dbg2")
      (value "SS210")
      (footprint "DO-214AC")
      (description "D - DIODE - SCHOTTKY - 100V - 2A")
      (fields (field (name "LCSC PART #") "C14996"))
      (libsource (lib "JLC_PCB") (part "SS210"))
    )
    (comp (ref "Dpsu1")
      (value "SS210")
      (footprint "DO-214AC")
      (description "D - DIODE - SCHOTTKY - 100V - 2A")
      (fields (field (name "LCSC PART #") "C14996"))
      (libsource (lib "JLC_PCB") (part "SS210"))
    )
    (comp (ref "Dsu1")
      (value "1N5819WS")
      (footprint "SOD-323")
      (description "D - DIODE - SCHOTTKY - 40V - 1A")
      (fields (field (name "LCSC PART #") "C191023"))
      (libsource (lib "JLC_PCB") (part "1N5819WS"))
    )
    (comp (ref "Dsu2")
      (value "1N5819WS")
      (footprint "SOD-323")
      (description "D - DIODE - SCHOTTKY - 40V - 1A")
      (fields (field (name "LCSC PART #") "C191023"))
      (libsource (lib "JLC_PCB") (part "1N5819WS"))
    )
    (comp (ref "Dtg1")
      (value "SS210")
      (footprint "DO-214AC")
      (description "D - DIODE - SCHOTTKY - 100V - 2A")
      (fields (field (name "LCSC PART #") "C14996"))
      (libsource (lib "JLC_PCB") (part "SS210"))
    )
    (comp (ref "Dtg2")
      (value "SS210")
      (footprint "DO-214AC")
      (description "D - DIODE - SCHOTTKY - 100V - 2A")
      (fields (field (name "LCSC PART #") "C14996"))
      (libsource (lib "JLC_PCB") (part "SS210"))
    )
    (comp (ref "D_1A")
      (value "N4148WS")
      (footprint "SOD-323")
      (description "D - DIODE - FAST TRR - 100V - 150mA - 4ns")
      (fields (field (name "LCSC PART #") "C2128"))
      (libsource (lib "JLC_PCB") (part "N4148WS"))
    )
    (comp (ref "D_1A_G")
      (value "ZMM5V6-M")
      (footprint "DO-213AA")
      (description "D - DIODE - ZENER - 5.6V - 500mW")
      (fields (field (name "LCSC PART #") "C8062"))
      (libsource (lib "JLC_PCB") (part "ZMM5V6-M"))
    )
    (comp (ref "D_1B")
      (value "N4148WS")
      (footprint "SOD-323")
      (description "D - DIODE - FAST TRR - 100V - 150mA - 4ns")
      (fields (field (name "LCSC PART #") "C2128"))
      (libsource (lib "JLC_PCB") (part "N4148WS"))
    )
    (comp (ref "D_1B_G")
      (value "ZMM5V6-M")
      (footprint "DO-213AA")
      (description "D - DIODE - ZENER - 5.6V - 500mW")
      (fields (field (name "LCSC PART #") "C8062"))
      (libsource (lib "JLC_PCB") (part "ZMM5V6-M"))
    )
    (comp (ref "D_CLAMP_1")
      (value "ZMM5V6-M")
      (footprint "DO-213AA")
      (description "D - DIODE - ZENER - 5.6V - 500mW")
      (fields (field (name "LCSC PART #") "C8062"))
      (libsource (lib "JLC_PCB") (part "ZMM5V6-M"))
    )
    (comp (ref "D_CLAMP_2")
      (value "ZMM5V6-M")
      (footprint "DO-213AA")
      (description "D - DIODE - ZENER - 5.6V - 500mW")
      (fields (field (name "LCSC PART #") "C8062"))
      (libsource (lib "JLC_PCB") (part "ZMM5V6-M"))
    )
    (comp (ref "D_CLAMP_3")
      (value "ZMM5V6-M")
      (footprint "DO-213AA")
      (description "D - DIODE - ZENER - 5.6V - 500mW")
      (fields (field (name "LCSC PART #") "C8062"))
      (libsource (lib "JLC_PCB") (part "ZMM5V6-M"))
    )
    (comp (ref "D_CLAMP_4")
      (value "ZMM5V6-M")
      (footprint "DO-213AA")
      (description "D - DIODE - ZENER - 5.6V - 500mW")
      (fields (field (name "LCSC PART #") "C8062"))
      (libsource (lib "JLC_PCB") (part "ZMM5V6-M"))
    )
    (comp (ref "D_CLAMP_5")
      (value "ZMM5V6-M")
      (footprint "DO-213AA")
      (description "D - DIODE - ZENER - 5.6V - 500mW")
      (fields (field (name "LCSC PART #") "C8062"))
      (libsource (lib "JLC_PCB") (part "ZMM5V6-M"))
    )
    (comp (ref "D_CLAMP_6")
      (value "ZMM5V6-M")
      (footprint "DO-213AA")
      (description "D - DIODE - ZENER - 5.6V - 500mW")
      (fields (field (name "LCSC PART #") "C8062"))
      (libsource (lib "JLC_PCB") (part "ZMM5V6-M"))
    )
    (comp (ref "D_CLAMP_7")
      (value "ZMM5V6-M")
      (footprint "DO-213AA")
      (description "D - DIODE - ZENER - 5.6V - 500mW")
      (fields (field (name "LCSC PART #") "C8062"))
      (libsource (lib "JLC_PCB") (part "ZMM5V6-M"))
    )
    (comp (ref "D_CLAMP_8")
      (value "ZMM5V6-M")
      (footprint "DO-213AA")
      (description "D - DIODE - ZENER - 5.6V - 500mW")
      (fields (field (name "LCSC PART #") "C8062"))
      (libsource (lib "JLC_PCB") (part "ZMM5V6-M"))
    )
    (comp (ref "D_CLAMP_9")
      (value "ZMM5V6-M")
      (footprint "DO-213AA")
      (description "D - DIODE - ZENER - 5.6V - 500mW")
      (fields (field (name "LCSC PART #") "C8062"))
      (libsource (lib "JLC_PCB") (part "ZMM5V6-M"))
    )
    (comp (ref "D_CLAMP_10")
      (value "ZMM5V6-M")
      (footprint "DO-213AA")
      (description "D - DIODE - ZENER - 5.6V - 500mW")
      (fields (field (name "LCSC PART #") "C8062"))
      (libsource (lib "JLC_PCB") (part "ZMM5V6-M"))
    )
    (comp (ref "D_CLAMP_11")
      (value "ZMM5V6-M")
      (footprint "DO-213AA")
      (description "D - DIODE - ZENER - 5.6V - 500mW")
      (fields (field (name "LCSC PART #") "C8062"))
      (libsource (lib "JLC_PCB") (part "ZMM5V6-M"))
    )
    (comp (ref "D_CLAMP_12")
      (value "ZMM5V6-M")
      (footprint "DO-213AA")
      (description "D - DIODE - ZENER - 5.6V - 500mW")
      (fields (field (name "LCSC PART #") "C8062"))
      (libsource (lib "JLC_PCB") (part "ZMM5V6-M"))
    )
    (comp (ref "D_CLAMP_13")
      (value "ZMM5V6-M")
      (footprint "DO-213AA")
      (description "D - DIODE - ZENER - 5.6V - 500mW")
      (fields (field (name "LCSC PART #") "C8062"))
      (libsource (lib "JLC_PCB") (part "ZMM5V6-M"))
    )
    (comp (ref "D_CLAMP_14")
      (value "ZMM5V6-M")
      (footprint "DO-213AA")
      (description "D - DIODE - ZENER - 5.6V - 500mW")
      (fields (field (name "LCSC PART #") "C8062"))
      (libsource (lib "JLC_PCB") (part "ZMM5V6-M"))
    )
    (comp (ref "D_CLAMP_15")
      (value "ZMM5V6-M")
      (footprint "DO-213AA")
      (description "D - DIODE - ZENER - 5.6V - 500mW")
      (fields (field (name "LCSC PART #") "C8062"))
      (libsource (lib "JLC_PCB") (part "ZMM5V6-M"))
    )
    (comp (ref "D_CLAMP_16")
      (value "ZMM5V6-M")
      (footprint "DO-213AA")
      (description "D - DIODE - ZENER - 5.6V - 500mW")
      (fields (field (name "LCSC PART #") "C8062"))
      (libsource (lib "JLC_PCB") (part "ZMM5V6-M"))
    )
    (comp (ref "D_CLAMP_17")
      (value "ZMM5V6-M")
      (footprint "DO-213AA")
      (description "D - DIODE - ZENER - 5.6V - 500mW")
      (fields (field (name "LCSC PART #") "C8062"))
      (libsource (lib "JLC_PCB") (part "ZMM5V6-M"))
    )
    (comp (ref "D_CLAMP_18")
      (value "ZMM5V6-M")
      (footprint "DO-213AA")
      (description "D - DIODE - ZENER - 5.6V - 500mW")
      (fields (field (name "LCSC PART #") "C8062"))
      (libsource (lib "JLC_PCB") (part "ZMM5V6-M"))
    )
    (comp (ref "J1")
      (value "2-406549-1")
      (footprint "TE_2-406549-1")
      (description "J - JACK - ETHERNET - Right - THT")
      (fields (field (name "LCSC PART #") "C125068"))
      (libsource (lib "JLC_PCB") (part "2-406549-1"))
    )
    (comp (ref "J2")
      (value "2-406549-1")
      (footprint "TE_2-406549-1")
      (description "J - JACK - ETHERNET - Right - THT")
      (fields (field (name "LCSC PART #") "C125068"))
      (libsource (lib "JLC_PCB") (part "2-406549-1"))
    )
    (comp (ref "Jout")
      (value "XT60PW_M")
      (footprint "XT60PW_M")
      (description "J - JACK - POWER - XT60 - RIGHT - MALE")
      (fields (field (name "LCSC PART #") "X"))
      (libsource (lib "JLC_PCB") (part "XT60PW_M"))
    )
    (comp (ref "L1")
      (value "220uH")
      (footprint "SRR1260")
      (description "L - INDUCTOR - 220uH - 1.6A - 12.5mm")
      (fields (field (name "LCSC PART #") "C169380") (field (name "Comment") "SWRB1207S-221MT"))
      (libsource (lib "JLC_PCB") (part "SWRB1207S-221MT"))
    )
    (comp (ref "L2")
      (value "220uH")
      (footprint "SRR1260")
      (description "L - INDUCTOR - 220uH - 1.6A - 12.5mm")
      (fields (field (name "LCSC PART #") "C169380") (field (name "Comment") "SWRB1207S-221MT"))
      (libsource (lib "JLC_PCB") (part "SWRB1207S-221MT"))
    )
    (comp (ref "L3")
      (value "220uH")
      (footprint "SRR1260")
      (description "L - INDUCTOR - 220uH - 1.6A - 12.5mm")
      (fields (field (name "LCSC PART #") "C169380") (field (name "Comment") "SWRB1207S-221MT"))
      (libsource (lib "JLC_PCB") (part "SWRB1207S-221MT"))
    )
    (comp (ref "L4")
      (value "220uH")
      (footprint "SRR1260")
      (description "L - INDUCTOR - 220uH - 1.6A - 12.5mm")
      (fields (field (name "LCSC PART #") "C169380") (field (name "Comment") "SWRB1207S-221MT"))
      (libsource (lib "JLC_PCB") (part "SWRB1207S-221MT"))
    )
    (comp (ref "L5")
      (value "220uH")
      (footprint "SRR1260")
      (description "L - INDUCTOR - 220uH - 1.6A - 12.5mm")
      (fields (field (name "LCSC PART #") "C169380") (field (name "Comment") "SWRB1207S-221MT"))
      (libsource (lib "JLC_PCB") (part "SWRB1207S-221MT"))
    )
    (comp (ref "L6")
      (value "220uH")
      (footprint "SRR1260")
      (description "L - INDUCTOR - 220uH - 1.6A - 12.5mm")
      (fields (field (name "LCSC PART #") "C169380") (field (name "Comment") "SWRB1207S-221MT"))
      (libsource (lib "JLC_PCB") (part "SWRB1207S-221MT"))
    )
    (comp (ref "L7")
      (value "220uH")
      (footprint "SRR1260")
      (description "L - INDUCTOR - 220uH - 1.6A - 12.5mm")
      (fields (field (name "LCSC PART #") "C169380") (field (name "Comment") "SWRB1207S-221MT"))
      (libsource (lib "JLC_PCB") (part "SWRB1207S-221MT"))
    )
    (comp (ref "L8")
      (value "220uH")
      (footprint "SRR1260")
      (description "L - INDUCTOR - 220uH - 1.6A - 12.5mm")
      (fields (field (name "LCSC PART #") "C169380") (field (name "Comment") "SWRB1207S-221MT"))
      (libsource (lib "JLC_PCB") (part "SWRB1207S-221MT"))
    )
    (comp (ref "L9")
      (value "220uH")
      (footprint "SRR1260")
      (description "L - INDUCTOR - 220uH - 1.6A - 12.5mm")
      (fields (field (name "LCSC PART #") "C169380") (field (name "Comment") "SWRB1207S-221MT"))
      (libsource (lib "JLC_PCB") (part "SWRB1207S-221MT"))
    )
    (comp (ref "L10")
      (value "220uH")
      (footprint "SRR1260")
      (description "L - INDUCTOR - 220uH - 1.6A - 12.5mm")
      (fields (field (name "LCSC PART #") "C169380") (field (name "Comment") "SWRB1207S-221MT"))
      (libsource (lib "JLC_PCB") (part "SWRB1207S-221MT"))
    )
    (comp (ref "L11")
      (value "220uH")
      (footprint "SRR1260")
      (description "L - INDUCTOR - 220uH - 1.6A - 12.5mm")
      (fields (field (name "LCSC PART #") "C169380") (field (name "Comment") "SWRB1207S-221MT"))
      (libsource (lib "JLC_PCB") (part "SWRB1207S-221MT"))
    )
    (comp (ref "L12")
      (value "220uH")
      (footprint "SRR1260")
      (description "L - INDUCTOR - 220uH - 1.6A - 12.5mm")
      (fields (field (name "LCSC PART #") "C169380") (field (name "Comment") "SWRB1207S-221MT"))
      (libsource (lib "JLC_PCB") (part "SWRB1207S-221MT"))
    )
    (comp (ref "L200")
      (value "220uH")
      (footprint "SRR1260")
      (description "L - INDUCTOR - 220uH - 1.6A - 12.5mm")
      (fields (field (name "LCSC PART #") "C169380") (field (name "Comment") "SWRB1207S-221MT"))
      (libsource (lib "JLC_PCB") (part "SWRB1207S-221MT"))
    )
    (comp (ref "Qbg1")
      (value "FDB33N25TM")
      (footprint "TO-263-3")
      (description "Q - TRANSISTOR - MOSFET (N) - 250V - 33A - 0.094R")
      (fields (field (name "LCSC PART #") "C241752"))
      (libsource (lib "JLC_PCB") (part "FDB33N25TM"))
    )
    (comp (ref "Qbg2")
      (value "FDB33N25TM")
      (footprint "TO-263-3")
      (description "Q - TRANSISTOR - MOSFET (N) - 250V - 33A - 0.094R")
      (fields (field (name "LCSC PART #") "C241752"))
      (libsource (lib "JLC_PCB") (part "FDB33N25TM"))
    )
    (comp (ref "Qscl")
      (value "2N7002")
      (footprint "TO-236AB")
      (description "Q - TRANSISTOR - MOSFET (N) - 60V - 200mW")
      (fields (field (name "LCSC PART #") "C8545"))
      (libsource (lib "JLC_PCB") (part "2N7002"))
    )
    (comp (ref "Qsda")
      (value "2N7002")
      (footprint "TO-236AB")
      (description "Q - TRANSISTOR - MOSFET (N) - 60V - 200mW")
      (fields (field (name "LCSC PART #") "C8545"))
      (libsource (lib "JLC_PCB") (part "2N7002"))
    )
    (comp (ref "Qsu")
      (value "MMBT3904")
      (footprint "TO-236AB")
      (description "Q - TRANSISTOR - BJT - NPN - 40V 200mA")
      (fields (field (name "LCSC PART #") "C20526"))
      (libsource (lib "JLC_PCB") (part "MMBT3904"))
    )
    (comp (ref "Qtg1")
      (value "FDB33N25TM")
      (footprint "TO-263-3")
      (description "Q - TRANSISTOR - MOSFET (N) - 250V - 33A - 0.094R")
      (fields (field (name "LCSC PART #") "C241752"))
      (libsource (lib "JLC_PCB") (part "FDB33N25TM"))
    )
    (comp (ref "Qtg2")
      (value "FDB33N25TM")
      (footprint "TO-263-3")
      (description "Q - TRANSISTOR - MOSFET (N) - 250V - 33A - 0.094R")
      (fields (field (name "LCSC PART #") "C241752"))
      (libsource (lib "JLC_PCB") (part "FDB33N25TM"))
    )
    (comp (ref "Q_LEDA")
      (value "2N7002")
      (footprint "TO-236AB")
      (description "Q - TRANSISTOR - MOSFET (N) - 60V - 200mW")
      (fields (field (name "LCSC PART #") "C8545"))
      (libsource (lib "JLC_PCB") (part "2N7002"))
    )
    (comp (ref "Q_LEDB")
      (value "2N7002")
      (footprint "TO-236AB")
      (description "Q - TRANSISTOR - MOSFET (N) - 60V - 200mW")
      (fields (field (name "LCSC PART #") "C8545"))
      (libsource (lib "JLC_PCB") (part "2N7002"))
    )
    (comp (ref "Q_LEDVSS")
      (value "2N7002")
      (footprint "TO-236AB")
      (description "Q - TRANSISTOR - MOSFET (N) - 60V - 200mW")
      (fields (field (name "LCSC PART #") "C8545"))
      (libsource (lib "JLC_PCB") (part "2N7002"))
    )
    (comp (ref "R1")
      (value "1m")
      (footprint "R_2512")
      (description "R - RESISTOR - SMD - 0.005R - 1% - 2512 - 2W")
      (fields (field (name "LCSC PART #") "C371096") (field (name "POWER") "2W"))
      (libsource (lib "JLC_PCB") (part "FMF25FPJR005-LH"))
    )
    (comp (ref "R10")
      (value "1m")
      (footprint "R_2512")
      (description "R - RESISTOR - SMD - 0.005R - 1% - 2512 - 2W")
      (fields (field (name "LCSC PART #") "C371096") (field (name "POWER") "2W"))
      (libsource (lib "JLC_PCB") (part "FMF25FPJR005-LH"))
    )
    (comp (ref "R21")
      (value "47R")
      (footprint "R_0402")
      (description "R - RESISTOR - SMD - 47R - 1% - 0402")
      (fields (field (name "LCSC PART #") "C25118") (field (name "Comment") "0402WGF470JTCE"))
      (libsource (lib "JLC_PCB") (part "0402WGF470JTCE"))
    )
    (comp (ref "R26")
      (value "10k")
      (footprint "R_0402")
      (description "R - RESISTOR - SMD - 10k - 1% - 0402")
      (fields (field (name "LCSC PART #") "C25744") (field (name "Comment") "0402WGF1002TCE"))
      (libsource (lib "JLC_PCB") (part "0402WGF1002TCE"))
    )
    (comp (ref "R28")
      (value "33k")
      (footprint "R_0402")
      (description "R - RESISTOR - SMD - 33k - 1% - 0402")
      (fields (field (name "LCSC PART #") "C25779") (field (name "Comment") "0402WGF3302TCE"))
      (libsource (lib "JLC_PCB") (part "0402WGF3302TCE"))
    )
    (comp (ref "R29")
      (value "0R")
      (footprint "R_0402")
      (description "R - RESISTOR - SMD - 0R - 1% - 0402")
      (fields (field (name "LCSC PART #") "C17168") (field (name "Comment") "0402WGF0000TCE"))
      (libsource (lib "JLC_PCB") (part "0402WGF0000TCE"))
    )
    (comp (ref "R30")
      (value "0R")
      (footprint "R_0402")
      (description "R - RESISTOR - SMD - 0R - 1% - 0402")
      (fields (field (name "LCSC PART #") "C17168") (field (name "Comment") "0402WGF0000TCE"))
      (libsource (lib "JLC_PCB") (part "0402WGF0000TCE"))
    )
    (comp (ref "R31")
      (value "0R")
      (footprint "R_0402")
      (description "R - RESISTOR - SMD - 0R - 1% - 0402")
      (fields (field (name "LCSC PART #") "C17168") (field (name "Comment") "0402WGF0000TCE"))
      (libsource (lib "JLC_PCB") (part "0402WGF0000TCE"))
    )
    (comp (ref "R38")
      (value "4.7k")
      (footprint "R_0402")
      (description "R - RESISTOR - SMD - 4.7k - 1% - 0402")
      (fields (field (name "LCSC PART #") "C25900") (field (name "Comment") "0402WGF4701TCE"))
      (libsource (lib "JLC_PCB") (part "0402WGF4701TCE"))
    )
    (comp (ref "R39")
      (value "1M")
      (footprint "R_0402")
      (description "R - RESISTOR - SMD - 1M - 1% - 0402")
      (fields (field (name "LCSC PART #") "C26083") (field (name "Comment") "0402WGF1004TCE"))
      (libsource (lib "JLC_PCB") (part "0402WGF1004TCE"))
    )
    (comp (ref "R40")
      (value "1M")
      (footprint "R_0402")
      (description "R - RESISTOR - SMD - 1M - 1% - 0402")
      (fields (field (name "LCSC PART #") "C26083") (field (name "Comment") "0402WGF1004TCE"))
      (libsource (lib "JLC_PCB") (part "0402WGF1004TCE"))
    )
    (comp (ref "R41")
      (value "1M")
      (footprint "R_0402")
      (description "R - RESISTOR - SMD - 1M - 1% - 0402")
      (fields (field (name "LCSC PART #") "C26083") (field (name "Comment") "0402WGF1004TCE"))
      (libsource (lib "JLC_PCB") (part "0402WGF1004TCE"))
    )
    (comp (ref "R45")
      (value "10k")
      (footprint "R_0402")
      (description "R - RESISTOR - SMD - 10k - 1% - 0402")
      (fields (field (name "LCSC PART #") "C25744") (field (name "Comment") "0402WGF1002TCE"))
      (libsource (lib "JLC_PCB") (part "0402WGF1002TCE"))
    )
    (comp (ref "R47")
      (value "10k")
      (footprint "R_0402")
      (description "R - RESISTOR - SMD - 10k - 1% - 0402")
      (fields (field (name "LCSC PART #") "C25744") (field (name "Comment") "0402WGF1002TCE"))
      (libsource (lib "JLC_PCB") (part "0402WGF1002TCE"))
    )
    (comp (ref "R48")
      (value "10k")
      (footprint "R_0402")
      (description "R - RESISTOR - SMD - 10k - 1% - 0402")
      (fields (field (name "LCSC PART #") "C25744") (field (name "Comment") "0402WGF1002TCE"))
      (libsource (lib "JLC_PCB") (part "0402WGF1002TCE"))
    )
    (comp (ref "R100")
      (value "100R")
      (footprint "R_0402")
      (description "R - RESISTOR - SMD - 100R - 1% - 0402")
      (fields (field (name "LCSC PART #") "C25076") (field (name "Comment") "0402WGF1000TCE"))
      (libsource (lib "JLC_PCB") (part "0402WGF1000TCE"))
    )
    (comp (ref "R101")
      (value "100R")
      (footprint "R_0402")
      (description "R - RESISTOR - SMD - 100R - 1% - 0402")
      (fields (field (name "LCSC PART #") "C25076") (field (name "Comment") "0402WGF1000TCE"))
      (libsource (lib "JLC_PCB") (part "0402WGF1000TCE"))
    )
    (comp (ref "R102")
      (value "100R")
      (footprint "R_0402")
      (description "R - RESISTOR - SMD - 100R - 1% - 0402")
      (fields (field (name "LCSC PART #") "C25076") (field (name "Comment") "0402WGF1000TCE"))
      (libsource (lib "JLC_PCB") (part "0402WGF1000TCE"))
    )
    (comp (ref "R103")
      (value "100R")
      (footprint "R_0402")
      (description "R - RESISTOR - SMD - 100R - 1% - 0402")
      (fields (field (name "LCSC PART #") "C25076") (field (name "Comment") "0402WGF1000TCE"))
      (libsource (lib "JLC_PCB") (part "0402WGF1000TCE"))
    )
    (comp (ref "R110")
      (value "10R")
      (footprint "R_1206")
      (description "R - RESISTOR - SMD - 10R - 1% - 1206")
      (fields (field (name "LCSC PART #") "C17903") (field (name "Comment") "1206W4F100JT5E"))
      (libsource (lib "JLC_PCB") (part "1206W4F100JT5E"))
    )
    (comp (ref "R140")
      (value "10R")
      (footprint "R_1206")
      (description "R - RESISTOR - SMD - 10R - 1% - 1206")
      (fields (field (name "LCSC PART #") "C17903") (field (name "Comment") "1206W4F100JT5E"))
      (libsource (lib "JLC_PCB") (part "1206W4F100JT5E"))
    )
    (comp (ref "R160")
      (value "0R")
      (footprint "R_0402")
      (description "R - RESISTOR - SMD - 0R - 1% - 0402")
      (fields (field (name "LCSC PART #") "C17168") (field (name "Comment") "0402WGF0000TCE"))
      (libsource (lib "JLC_PCB") (part "0402WGF0000TCE"))
    )
    (comp (ref "Ragnd")
      (value "0R")
      (footprint "R_0402")
      (description "R - RESISTOR - SMD - 0R - 1% - 0402")
      (fields (field (name "LCSC PART #") "C17168") (field (name "Comment") "0402WGF0000TCE"))
      (libsource (lib "JLC_PCB") (part "0402WGF0000TCE"))
    )
    (comp (ref "Rbg1a")
      (value "10R")
      (footprint "R_0402")
      (description "R - RESISTOR - SMD - 10R - 1% - 0402")
      (fields (field (name "LCSC PART #") "C25077") (field (name "Comment") "0402WGF100JTCE"))
      (libsource (lib "JLC_PCB") (part "0402WGF100JTCE"))
    )
    (comp (ref "Rbg1b")
      (value "10R")
      (footprint "R_0402")
      (description "R - RESISTOR - SMD - 10R - 1% - 0402")
      (fields (field (name "LCSC PART #") "C25077") (field (name "Comment") "0402WGF100JTCE"))
      (libsource (lib "JLC_PCB") (part "0402WGF100JTCE"))
    )
    (comp (ref "Rbg1s")
      (value "10k")
      (footprint "R_0402")
      (description "R - RESISTOR - SMD - 10k - 1% - 0402")
      (fields (field (name "LCSC PART #") "C25744") (field (name "Comment") "0402WGF1002TCE"))
      (libsource (lib "JLC_PCB") (part "0402WGF1002TCE"))
    )
    (comp (ref "Rbg2a")
      (value "10R")
      (footprint "R_0402")
      (description "R - RESISTOR - SMD - 10R - 1% - 0402")
      (fields (field (name "LCSC PART #") "C25077") (field (name "Comment") "0402WGF100JTCE"))
      (libsource (lib "JLC_PCB") (part "0402WGF100JTCE"))
    )
    (comp (ref "Rbg2b")
      (value "10R")
      (footprint "R_0402")
      (description "R - RESISTOR - SMD - 10R - 1% - 0402")
      (fields (field (name "LCSC PART #") "C25077") (field (name "Comment") "0402WGF100JTCE"))
      (libsource (lib "JLC_PCB") (part "0402WGF100JTCE"))
    )
    (comp (ref "Rbg2s")
      (value "10k")
      (footprint "R_0402")
      (description "R - RESISTOR - SMD - 10k - 1% - 0402")
      (fields (field (name "LCSC PART #") "C25744") (field (name "Comment") "0402WGF1002TCE"))
      (libsource (lib "JLC_PCB") (part "0402WGF1002TCE"))
    )
    (comp (ref "Rbin")
      (value "10R")
      (footprint "R_0402")
      (description "R - RESISTOR - SMD - 10R - 1% - 0402")
      (fields (field (name "LCSC PART #") "C25077") (field (name "Comment") "0402WGF100JTCE"))
      (libsource (lib "JLC_PCB") (part "0402WGF100JTCE"))
    )
    (comp (ref "Rbout")
      (value "10R")
      (footprint "R_0402")
      (description "R - RESISTOR - SMD - 10R - 1% - 0402")
      (fields (field (name "LCSC PART #") "C25077") (field (name "Comment") "0402WGF100JTCE"))
      (libsource (lib "JLC_PCB") (part "0402WGF100JTCE"))
    )
    (comp (ref "Rcl1")
      (value "33k")
      (footprint "R_0402")
      (description "R - RESISTOR - SMD - 33k - 1% - 0402")
      (fields (field (name "LCSC PART #") "C25779") (field (name "Comment") "0402WGF3302TCE"))
      (libsource (lib "JLC_PCB") (part "0402WGF3302TCE"))
    )
    (comp (ref "Rcl2")
      (value "100k")
      (footprint "R_0402")
      (description "R - RESISTOR - SMD - 100k - 1% -  0402")
      (fields (field (name "LCSC PART #") "C25741") (field (name "Comment") "0402WGF1003TCE"))
      (libsource (lib "JLC_PCB") (part "0402WGF1003TCE"))
    )
    (comp (ref "Rcs")
      (value "1m")
      (footprint "R_2512")
      (description "R - RESISTOR - SMD - 0.005R - 1% - 2512 - 2W")
      (fields (field (name "LCSC PART #") "C371096") (field (name "POWER") "2W"))
      (libsource (lib "JLC_PCB") (part "FMF25FPJR005-LH"))
    )
    (comp (ref "Rcsg")
      (value "100R")
      (footprint "R_0402")
      (description "R - RESISTOR - SMD - 100R - 1% - 0402")
      (fields (field (name "LCSC PART #") "C25076") (field (name "Comment") "0402WGF1000TCE"))
      (libsource (lib "JLC_PCB") (part "0402WGF1000TCE"))
    )
    (comp (ref "Rcsp")
      (value "100R")
      (footprint "R_0402")
      (description "R - RESISTOR - SMD - 100R - 1% - 0402")
      (fields (field (name "LCSC PART #") "C25076") (field (name "Comment") "0402WGF1000TCE"))
      (libsource (lib "JLC_PCB") (part "0402WGF1000TCE"))
    )
    (comp (ref "Riin")
      (value "56k")
      (footprint "R_0402")
      (description "R - RESISTOR - SMD - 56k - 1% - 0402")
      (fields (field (name "LCSC PART #") "C25796") (field (name "Comment") "0402WGF5602TCE"))
      (libsource (lib "JLC_PCB") (part "0402WGF5602TCE"))
    )
    (comp (ref "Riinsns1")
      (value "680R")
      (footprint "R_0603")
      (description "R - RESISTOR - SMD - 680R - 1% - 0603")
      (fields (field (name "LCSC PART #") "C23228") (field (name "Comment") "0603WAF6800T5E"))
      (libsource (lib "JLC_PCB") (part "0603WAF6800T5E"))
    )
    (comp (ref "Riinsns2")
      (value "680R")
      (footprint "R_0603")
      (description "R - RESISTOR - SMD - 680R - 1% - 0603")
      (fields (field (name "LCSC PART #") "C23228") (field (name "Comment") "0603WAF6800T5E"))
      (libsource (lib "JLC_PCB") (part "0603WAF6800T5E"))
    )
    (comp (ref "Riout")
      (value "56k")
      (footprint "R_0402")
      (description "R - RESISTOR - SMD - 56k - 1% - 0402")
      (fields (field (name "LCSC PART #") "C25796") (field (name "Comment") "0402WGF5602TCE"))
      (libsource (lib "JLC_PCB") (part "0402WGF5602TCE"))
    )
    (comp (ref "Rioutsns1")
      (value "680R")
      (footprint "R_0603")
      (description "R - RESISTOR - SMD - 680R - 1% - 0603")
      (fields (field (name "LCSC PART #") "C23228") (field (name "Comment") "0603WAF6800T5E"))
      (libsource (lib "JLC_PCB") (part "0603WAF6800T5E"))
    )
    (comp (ref "Rioutsns2")
      (value "680R")
      (footprint "R_0603")
      (description "R - RESISTOR - SMD - 680R - 1% - 0603")
      (fields (field (name "LCSC PART #") "C23228") (field (name "Comment") "0603WAF6800T5E"))
      (libsource (lib "JLC_PCB") (part "0603WAF6800T5E"))
    )
    (comp (ref "Rnc4")
      (value "56k")
      (footprint "R_0402")
      (description "R - RESISTOR - SMD - 56k - 1% - 0402")
      (fields (field (name "LCSC PART #") "C25796") (field (name "Comment") "0402WGF5602TCE"))
      (libsource (lib "JLC_PCB") (part "0402WGF5602TCE"))
    )
    (comp (ref "Ron")
      (value "200k")
      (footprint "R_0402")
      (description "R - RESISTOR - SMD - 200k - 1% - 0402")
      (fields (field (name "LCSC PART #") "C25764") (field (name "Comment") "0402WGF2003TCE"))
      (libsource (lib "JLC_PCB") (part "0402WGF2003TCE"))
    )
    (comp (ref "Ron_c")
      (value "47k")
      (footprint "R_0402")
      (description "R - RESISTOR - SMD - 47k - 1% - 0402")
      (fields (field (name "LCSC PART #") "C25792") (field (name "Comment") "0402WGF4702TCE"))
      (libsource (lib "JLC_PCB") (part "0402WGF4702TCE"))
    )
    (comp (ref "Rovs")
      (value "10k")
      (footprint "R_0402")
      (description "R - RESISTOR - SMD - 10k - 1% - 0402")
      (fields (field (name "LCSC PART #") "C25744") (field (name "Comment") "0402WGF1002TCE"))
      (libsource (lib "JLC_PCB") (part "0402WGF1002TCE"))
    )
    (comp (ref "Rpm")
      (value "56k")
      (footprint "R_0402")
      (description "R - RESISTOR - SMD - 56k - 1% - 0402")
      (fields (field (name "LCSC PART #") "C25796") (field (name "Comment") "0402WGF5602TCE"))
      (libsource (lib "JLC_PCB") (part "0402WGF5602TCE"))
    )
    (comp (ref "Rpsu1")
      (value "0R")
      (footprint "R_0402")
      (description "R - RESISTOR - SMD - 0R - 1% - 0402")
      (fields (field (name "LCSC PART #") "C17168") (field (name "Comment") "0402WGF0000TCE"))
      (libsource (lib "JLC_PCB") (part "0402WGF0000TCE"))
    )
    (comp (ref "Rpsu2")
      (value "0R")
      (footprint "R_0402")
      (description "R - RESISTOR - SMD - 0R - 1% - 0402")
      (fields (field (name "LCSC PART #") "C17168") (field (name "Comment") "0402WGF0000TCE"))
      (libsource (lib "JLC_PCB") (part "0402WGF0000TCE"))
    )
    (comp (ref "Rpsufb1")
      (value "10k")
      (footprint "R_0402")
      (description "R - RESISTOR - SMD - 10k - 1% - 0402")
      (fields (field (name "LCSC PART #") "C25744") (field (name "Comment") "0402WGF1002TCE"))
      (libsource (lib "JLC_PCB") (part "0402WGF1002TCE"))
    )
    (comp (ref "Rpsufb2")
      (value "3.3k")
      (footprint "R_0402")
      (description "R - RESISTOR - SMD - 3.3k - 1% - 0402")
      (fields (field (name "LCSC PART #") "C25890") (field (name "Comment") "0402WGF3301TCE"))
      (libsource (lib "JLC_PCB") (part "0402WGF3301TCE"))
    )
    (comp (ref "Rrst")
      (value "1k")
      (footprint "R_0402")
      (description "R - RESISTOR - SMD - 1k - 1% - 0402")
      (fields (field (name "LCSC PART #") "C11702") (field (name "Comment") "0402WGF1001TCE"))
      (libsource (lib "JLC_PCB") (part "0402WGF1001TCE"))
    )
    (comp (ref "Rscl")
      (value "10k")
      (footprint "R_0402")
      (description "R - RESISTOR - SMD - 10k - 1% - 0402")
      (fields (field (name "LCSC PART #") "C25744") (field (name "Comment") "0402WGF1002TCE"))
      (libsource (lib "JLC_PCB") (part "0402WGF1002TCE"))
    )
    (comp (ref "Rsda")
      (value "10k")
      (footprint "R_0402")
      (description "R - RESISTOR - SMD - 10k - 1% - 0402")
      (fields (field (name "LCSC PART #") "C25744") (field (name "Comment") "0402WGF1002TCE"))
      (libsource (lib "JLC_PCB") (part "0402WGF1002TCE"))
    )
    (comp (ref "Rsu1")
      (value "100k")
      (footprint "R_0402")
      (description "R - RESISTOR - SMD - 100k - 1% -  0402")
      (fields (field (name "LCSC PART #") "C25741") (field (name "Comment") "0402WGF1003TCE"))
      (libsource (lib "JLC_PCB") (part "0402WGF1003TCE"))
    )
    (comp (ref "Rsu2")
      (value "270k")
      (footprint "R_0603")
      (description "R - RESISTOR - SMD - 270k - 1% - 0603")
      (fields (field (name "LCSC PART #") "C22965") (field (name "Comment") "0603WAF2703T5E"))
      (libsource (lib "JLC_PCB") (part "0603WAF2703T5E"))
    )
    (comp (ref "Rsu3")
      (value "270k")
      (footprint "R_0603")
      (description "R - RESISTOR - SMD - 270k - 1% - 0603")
      (fields (field (name "LCSC PART #") "C22965") (field (name "Comment") "0603WAF2703T5E"))
      (libsource (lib "JLC_PCB") (part "0603WAF2703T5E"))
    )
    (comp (ref "Rsu4")
      (value "330K")
      (footprint "R_0402")
      (description "R - RESISTOR - SMD - 330k - 1% - 0402")
      (fields (field (name "LCSC PART #") "C25778") (field (name "Comment") "0402WGF3303TCE"))
      (libsource (lib "JLC_PCB") (part "0402WGF3303TCE"))
    )
    (comp (ref "Rsu5")
      (value "1k")
      (footprint "R_0402")
      (description "R - RESISTOR - SMD - 1k - 1% - 0402")
      (fields (field (name "LCSC PART #") "C11702") (field (name "Comment") "0402WGF1001TCE"))
      (libsource (lib "JLC_PCB") (part "0402WGF1001TCE"))
    )
    (comp (ref "Rtg1a")
      (value "10R")
      (footprint "R_0402")
      (description "R - RESISTOR - SMD - 10R - 1% - 0402")
      (fields (field (name "LCSC PART #") "C25077") (field (name "Comment") "0402WGF100JTCE"))
      (libsource (lib "JLC_PCB") (part "0402WGF100JTCE"))
    )
    (comp (ref "Rtg1b")
      (value "10R")
      (footprint "R_0402")
      (description "R - RESISTOR - SMD - 10R - 1% - 0402")
      (fields (field (name "LCSC PART #") "C25077") (field (name "Comment") "0402WGF100JTCE"))
      (libsource (lib "JLC_PCB") (part "0402WGF100JTCE"))
    )
    (comp (ref "Rtg1s")
      (value "10k")
      (footprint "R_0402")
      (description "R - RESISTOR - SMD - 10k - 1% - 0402")
      (fields (field (name "LCSC PART #") "C25744") (field (name "Comment") "0402WGF1002TCE"))
      (libsource (lib "JLC_PCB") (part "0402WGF1002TCE"))
    )
    (comp (ref "Rtg2a")
      (value "10R")
      (footprint "R_0402")
      (description "R - RESISTOR - SMD - 10R - 1% - 0402")
      (fields (field (name "LCSC PART #") "C25077") (field (name "Comment") "0402WGF100JTCE"))
      (libsource (lib "JLC_PCB") (part "0402WGF100JTCE"))
    )
    (comp (ref "Rtg2b")
      (value "10R")
      (footprint "R_0402")
      (description "R - RESISTOR - SMD - 10R - 1% - 0402")
      (fields (field (name "LCSC PART #") "C25077") (field (name "Comment") "0402WGF100JTCE"))
      (libsource (lib "JLC_PCB") (part "0402WGF100JTCE"))
    )
    (comp (ref "Rtg2s")
      (value "10k")
      (footprint "R_0402")
      (description "R - RESISTOR - SMD - 10k - 1% - 0402")
      (fields (field (name "LCSC PART #") "C25744") (field (name "Comment") "0402WGF1002TCE"))
      (libsource (lib "JLC_PCB") (part "0402WGF1002TCE"))
    )
    (comp (ref "Rvinb")
      (value "10k")
      (footprint "R_0603")
      (description "R - RESISTOR - SMD - 10k - 1% - 0603")
      (fields (field (name "LCSC PART #") "C25804") (field (name "Comment") "0603WAF1002T5E"))
      (libsource (lib "JLC_PCB") (part "0603WAF1002T5E"))
    )
    (comp (ref "Rvint")
      (value "100k")
      (footprint "R_0603")
      (description "R - RESISTOR - SMD - 100k - 1% -  0603")
      (fields (field (name "LCSC PART #") "C22936") (field (name "Comment") "0603WAF1003T5E"))
      (libsource (lib "JLC_PCB") (part "0603WAF100KT5E"))
    )
    (comp (ref "Rvoutb")
      (value "10k")
      (footprint "R_0603")
      (description "R - RESISTOR - SMD - 10k - 1% - 0603")
      (fields (field (name "LCSC PART #") "C25804") (field (name "Comment") "0603WAF1002T5E"))
      (libsource (lib "JLC_PCB") (part "0603WAF1002T5E"))
    )
    (comp (ref "Rvoutt")
      (value "100k")
      (footprint "R_0603")
      (description "R - RESISTOR - SMD - 100k - 1% -  0603")
      (fields (field (name "LCSC PART #") "C22936") (field (name "Comment") "0603WAF1003T5E"))
      (libsource (lib "JLC_PCB") (part "0603WAF100KT5E"))
    )
    (comp (ref "R_1A_a")
      (value "47k")
      (footprint "R_0402")
      (description "R - RESISTOR - SMD - 47k - 1% - 0402")
      (fields (field (name "LCSC PART #") "C25792") (field (name "Comment") "0402WGF4702TCE"))
      (libsource (lib "JLC_PCB") (part "0402WGF4702TCE"))
    )
    (comp (ref "R_1A_b")
      (value "47k")
      (footprint "R_0402")
      (description "R - RESISTOR - SMD - 47k - 1% - 0402")
      (fields (field (name "LCSC PART #") "C25792") (field (name "Comment") "0402WGF4702TCE"))
      (libsource (lib "JLC_PCB") (part "0402WGF4702TCE"))
    )
    (comp (ref "R_1A_c")
      (value "100k")
      (footprint "R_0402")
      (description "R - RESISTOR - SMD - 100k - 1% -  0402")
      (fields (field (name "LCSC PART #") "C25741") (field (name "Comment") "0402WGF1003TCE"))
      (libsource (lib "JLC_PCB") (part "0402WGF1003TCE"))
    )
    (comp (ref "R_1B_a")
      (value "47k")
      (footprint "R_0402")
      (description "R - RESISTOR - SMD - 47k - 1% - 0402")
      (fields (field (name "LCSC PART #") "C25792") (field (name "Comment") "0402WGF4702TCE"))
      (libsource (lib "JLC_PCB") (part "0402WGF4702TCE"))
    )
    (comp (ref "R_1B_b")
      (value "47k")
      (footprint "R_0402")
      (description "R - RESISTOR - SMD - 47k - 1% - 0402")
      (fields (field (name "LCSC PART #") "C25792") (field (name "Comment") "0402WGF4702TCE"))
      (libsource (lib "JLC_PCB") (part "0402WGF4702TCE"))
    )
    (comp (ref "R_1B_c")
      (value "100k")
      (footprint "R_0402")
      (description "R - RESISTOR - SMD - 100k - 1% -  0402")
      (fields (field (name "LCSC PART #") "C25741") (field (name "Comment") "0402WGF1003TCE"))
      (libsource (lib "JLC_PCB") (part "0402WGF1003TCE"))
    )
    (comp (ref "R_LEDA_O")
      (value "0R")
      (footprint "R_0402")
      (description "R - RESISTOR - SMD - 0R - 1% - 0402")
      (fields (field (name "LCSC PART #") "C17168") (field (name "Comment") "0402WGF0000TCE"))
      (libsource (lib "JLC_PCB") (part "0402WGF0000TCE"))
    )
    (comp (ref "R_LEDB_O")
      (value "0R")
      (footprint "R_0402")
      (description "R - RESISTOR - SMD - 0R - 1% - 0402")
      (fields (field (name "LCSC PART #") "C17168") (field (name "Comment") "0402WGF0000TCE"))
      (libsource (lib "JLC_PCB") (part "0402WGF0000TCE"))
    )
    (comp (ref "SWrst")
      (value "TS-1187A-C-C-B")
      (footprint "TS-1187A-C-C-B")
      (description "SW - SWITCH - SPST - NO - Top Actuated Surface Mount")
      (fields (field (name "LCSC PART #") "C318889"))
      (libsource (lib "JLC_PCB") (part "TS-1187A-C-C-B"))
    )
    (comp (ref "U5V2")
      (value "78L05G-AB3-R")
      (footprint "SOT-223-3")
      (description "U - IC - 5V Power Regulator")
      (fields (field (name "LCSC PART #") "C71136"))
      (libsource (lib "JLC_PCB") (part "78L05G-AB3-R"))
    )
    (comp (ref "U8")
      (value "SM72442MTE/NOPB")
      (footprint "MTC28_L")
      (description "Programmable Maximum Power Point Tracking Controller for Photovoltaic Solar Panels")
      (fields (field (name "MANUFACTURER") "National Semiconductor") (field (name "PARTNUMBER") "SM72442"))
      (libsource (lib "SM_ICs") (part "SM72442"))
    )
    (comp (ref "Ugd")
      (value "SM72295MAX")
      (footprint "M28B_M")
      (description "Photovoltaic Full Bridge Driver")
      (fields (field (name "MANUFACTURER") "National Semiconductor") (field (name "PARTNUMBER") "SM72295"))
      (libsource (lib "JLC_PCB") (part "SM72295"))
    )
    (comp (ref "Upsu")
      (value "LM5008MMX/NOPB")
      (footprint "SOP65P490X110-8N")
      (description "U - IC - BUCK CONVERTER, ADJUSTABLE, 95V, 350mA")
      (libsource (lib "JLC_PCB") (part "LM5008MMX/NOPB"))
    )
    (comp (ref "Urst")
      (value "TL7705ACD")
      (footprint "SOIC-8-P1.27-W3.5")
      (description "U - IC - 5-V single-supply voltage supervisor with programmable delay time 8-PDIP 0 to 70")
      (fields (field (name "MP") "TL7705ACP") (field (name "MF") "Texas Instruments"))
      (libsource (lib "JLC_PCB") (part "TL7705ACD"))
    )
  )
  (nets
    (net (code "1") (name "+5V") (class "Default")
      (node (ref "C34") (pin "2") (pinfunction "2_2") (pintype "passive"))
      (node (ref "C37") (pin "1") (pinfunction "1_1") (pintype "passive"))
      (node (ref "C5v2") (pin "2") (pinfunction "2_2") (pintype "passive"))
      (node (ref "Cvdd") (pin "2") (pinfunction "2_2") (pintype "passive"))
      (node (ref "Qsu") (pin "3") (pinfunction "C_3") (pintype "passive"))
      (node (ref "R100") (pin "1") (pinfunction "1_1") (pintype "passive"))
      (node (ref "R101") (pin "1") (pinfunction "1_1") (pintype "passive"))
      (node (ref "R102") (pin "1") (pinfunction "1_1") (pintype "passive"))
      (node (ref "R103") (pin "1") (pinfunction "1_1") (pintype "passive"))
      (node (ref "R21") (pin "2") (pinfunction "2_2") (pintype "passive"))
      (node (ref "R26") (pin "2") (pinfunction "2_2") (pintype "passive"))
      (node (ref "R28") (pin "2") (pinfunction "2_2") (pintype "passive"))
      (node (ref "R29") (pin "2") (pinfunction "2_2") (pintype "passive"))
      (node (ref "R30") (pin "1") (pinfunction "1_1") (pintype "passive"))
      (node (ref "R31") (pin "2") (pinfunction "2_2") (pintype "passive"))
      (node (ref "R45") (pin "1") (pinfunction "1_1") (pintype "passive"))
      (node (ref "R47") (pin "2") (pinfunction "2_2") (pintype "passive"))
      (node (ref "R48") (pin "2") (pinfunction "2_2") (pintype "passive"))
      (node (ref "Rnc4") (pin "2") (pinfunction "2_2") (pintype "passive"))
      (node (ref "Rpm") (pin "1") (pinfunction "1_1") (pintype "passive"))
      (node (ref "Rrst") (pin "2") (pinfunction "2_2") (pintype "passive"))
      (node (ref "Rsu4") (pin "2") (pinfunction "2_2") (pintype "passive"))
      (node (ref "U5V2") (pin "1") (pinfunction "Vout_1") (pintype "output"))
      (node (ref "U8") (pin "3") (pinfunction "VDDD_3") (pintype "power_in"))
      (node (ref "U8") (pin "6") (pinfunction "I2C0_6") (pintype "bidirectional"))
      (node (ref "Ugd") (pin "17") (pinfunction "VDD_17") (pintype "power_in"))
      (node (ref "Urst") (pin "7") (pinfunction "SENSE_7") (pintype "input"))
      (node (ref "Urst") (pin "8") (pinfunction "VCC_8") (pintype "power_in"))
    )
    (net (code "2") (name "+10V") (class "Default")
      (node (ref "C12v1") (pin "1") (pinfunction "1_1") (pintype "passive"))
      (node (ref "C12v10") (pin "1") (pinfunction "1_1") (pintype "passive"))
      (node (ref "C12v11") (pin "1") (pinfunction "1_1") (pintype "passive"))
      (node (ref "C12v12") (pin "1") (pinfunction "1_1") (pintype "passive"))
      (node (ref "C12v2") (pin "1") (pinfunction "1_1") (pintype "passive"))
      (node (ref "C12v3") (pin "1") (pinfunction "1_1") (pintype "passive"))
      (node (ref "C12v4") (pin "1") (pinfunction "1_1") (pintype "passive"))
      (node (ref "C12v5") (pin "1") (pinfunction "1_1") (pintype "passive"))
      (node (ref "C12v6") (pin "1") (pinfunction "1_1") (pintype "passive"))
      (node (ref "C12v7") (pin "1") (pinfunction "1_1") (pintype "passive"))
      (node (ref "C12v8") (pin "1") (pinfunction "1_1") (pintype "passive"))
      (node (ref "C12v9") (pin "1") (pinfunction "1_1") (pintype "passive"))
      (node (ref "C5v1") (pin "2") (pinfunction "2_2") (pintype "passive"))
      (node (ref "Ccmp") (pin "2") (pinfunction "2_2") (pintype "passive"))
      (node (ref "Cvcc") (pin "2") (pinfunction "2_2") (pintype "passive"))
      (node (ref "L200") (pin "2") (pinfunction "2_2") (pintype "passive"))
      (node (ref "Rpsufb1") (pin "1") (pinfunction "1_1") (pintype "passive"))
      (node (ref "U5V2") (pin "3") (pinfunction "VIN_3") (pintype "input"))
      (node (ref "Ugd") (pin "21") (pinfunction "VCC1_21") (pintype "power_in"))
      (node (ref "Ugd") (pin "25") (pinfunction "VCC2_25") (pintype "power_in"))
    )
    (net (code "3") (name "/1A_GATE") (class "Default")
      (node (ref "D_1A") (pin "2") (pinfunction "A_2") (pintype "passive"))
      (node (ref "D_1A_G") (pin "1") (pinfunction "K_1") (pintype "passive"))
      (node (ref "Q_LEDA") (pin "1") (pinfunction "G_1") (pintype "passive"))
      (node (ref "R_1A_b") (pin "2") (pinfunction "2_2") (pintype "passive"))
      (node (ref "R_1A_c") (pin "2") (pinfunction "2_2") (pintype "passive"))
    )
    (net (code "4") (name "/1B_GATE") (class "Default")
      (node (ref "D_1B") (pin "2") (pinfunction "A_2") (pintype "passive"))
      (node (ref "D_1B_G") (pin "1") (pinfunction "K_1") (pintype "passive"))
      (node (ref "R_1B_b") (pin "2") (pinfunction "2_2") (pintype "passive"))
      (node (ref "R_1B_c") (pin "2") (pinfunction "2_2") (pintype "passive"))
    )
    (net (code "5") (name "/3V3_SCL") (class "Default")
      (node (ref "Qscl") (pin "2") (pinfunction "S_2") (pintype "passive"))
      (node (ref "Rscl") (pin "1") (pinfunction "1_1") (pintype "passive"))
    )
    (net (code "6") (name "/3V3_SDA") (class "Default")
      (node (ref "Qsda") (pin "2") (pinfunction "S_2") (pintype "passive"))
      (node (ref "Rsda") (pin "1") (pinfunction "1_1") (pintype "passive"))
    )
    (net (code "7") (name "/5V_SCL") (class "Default")
      (node (ref "Qscl") (pin "3") (pinfunction "D_3") (pintype "passive"))
      (node (ref "R48") (pin "1") (pinfunction "1_1") (pintype "passive"))
      (node (ref "U8") (pin "8") (pinfunction "SCL_8") (pintype "input"))
    )
    (net (code "8") (name "/5V_SDA") (class "Default")
      (node (ref "Qsda") (pin "3") (pinfunction "D_3") (pintype "passive"))
      (node (ref "R47") (pin "1") (pinfunction "1_1") (pintype "passive"))
      (node (ref "U8") (pin "9") (pinfunction "SDA_9") (pintype "bidirectional"))
    )
    (net (code "9") (name "/BG1") (class "Default")
      (node (ref "D5") (pin "1") (pinfunction "K_1") (pintype "passive"))
      (node (ref "Rbg1a") (pin "1") (pinfunction "1_1") (pintype "passive"))
      (node (ref "Rbg1b") (pin "1") (pinfunction "1_1") (pintype "passive"))
      (node (ref "Ugd") (pin "24") (pinfunction "LOA_24") (pintype "output"))
    )
    (net (code "10") (name "/BG2") (class "Default")
      (node (ref "D6") (pin "1") (pinfunction "K_1") (pintype "passive"))
      (node (ref "Rbg2a") (pin "2") (pinfunction "2_2") (pintype "passive"))
      (node (ref "Rbg2b") (pin "2") (pinfunction "2_2") (pintype "passive"))
      (node (ref "Ugd") (pin "22") (pinfunction "LOB_22") (pintype "output"))
    )
    (net (code "11") (name "/BIN") (class "Default")
      (node (ref "Rbin") (pin "2") (pinfunction "2_2") (pintype "passive"))
      (node (ref "Ugd") (pin "4") (pinfunction "BIN_4") (pintype "output"))
    )
    (net (code "12") (name "/BIN_R") (class "Default")
      (node (ref "Csu2") (pin "2") (pinfunction "2_2") (pintype "passive"))
      (node (ref "Qsu") (pin "2") (pinfunction "E_2") (pintype "passive"))
      (node (ref "Rbin") (pin "1") (pinfunction "1_1") (pintype "passive"))
      (node (ref "Rsu1") (pin "2") (pinfunction "2_2") (pintype "passive"))
      (node (ref "U8") (pin "19") (pinfunction "AIIN_19") (pintype "input"))
    )
    (net (code "13") (name "/BOOST1") (class "Default")
      (node (ref "Cboot1") (pin "2") (pinfunction "2_2") (pintype "passive"))
      (node (ref "Ugd") (pin "26") (pinfunction "HBA_26") (pintype "passive"))
    )
    (net (code "14") (name "/BOOST2") (class "Default")
      (node (ref "Cboot2") (pin "2") (pinfunction "2_2") (pintype "passive"))
      (node (ref "Ugd") (pin "20") (pinfunction "HBB_20") (pintype "passive"))
    )
    (net (code "15") (name "/BOUT") (class "Default")
      (node (ref "Rbout") (pin "2") (pinfunction "2_2") (pintype "passive"))
      (node (ref "Ugd") (pin "11") (pinfunction "BOUT_11") (pintype "output"))
    )
    (net (code "16") (name "/BOUT_R") (class "Default")
      (node (ref "Rbout") (pin "1") (pinfunction "1_1") (pintype "passive"))
      (node (ref "U8") (pin "21") (pinfunction "AIOUT_21") (pintype "output"))
    )
    (net (code "17") (name "/BST_SIM") (class "Default")
      (node (ref "Dsu1") (pin "1") (pinfunction "K_1") (pintype "passive"))
      (node (ref "Dsu2") (pin "2") (pinfunction "A_2") (pintype "passive"))
      (node (ref "Rsu5") (pin "1") (pinfunction "1_1") (pintype "passive"))
    )
    (net (code "18") (name "/CSN") (class "Default")
      (node (ref "C14") (pin "1") (pinfunction "1_1") (pintype "passive"))
      (node (ref "CCS") (pin "1") (pinfunction "1_1") (pintype "passive"))
      (node (ref "Rcsg") (pin "1") (pinfunction "1_1") (pintype "passive"))
    )
    (net (code "19") (name "/CSP") (class "Default")
      (node (ref "C15") (pin "1") (pinfunction "1_1") (pintype "passive"))
      (node (ref "CCS") (pin "2") (pinfunction "2_2") (pintype "passive"))
      (node (ref "Rcsp") (pin "1") (pinfunction "1_1") (pintype "passive"))
    )
    (net (code "20") (name "/D8") (class "Default")
      (node (ref "D_CLAMP_8") (pin "2") (pinfunction "A_2") (pintype "passive"))
      (node (ref "D_CLAMP_9") (pin "1") (pinfunction "K_1") (pintype "passive"))
      (node (ref "R160") (pin "1") (pinfunction "1_1") (pintype "passive"))
    )
    (net (code "21") (name "/D10") (class "Default")
      (node (ref "D_CLAMP_10") (pin "2") (pinfunction "A_2") (pintype "passive"))
      (node (ref "D_CLAMP_11") (pin "1") (pinfunction "K_1") (pintype "passive"))
      (node (ref "R160") (pin "2") (pinfunction "2_2") (pintype "passive"))
    )
    (net (code "22") (name "/FBIN") (class "Default")
      (node (ref "C29") (pin "2") (pinfunction "2_2") (pintype "passive"))
      (node (ref "Dsu2") (pin "1") (pinfunction "K_1") (pintype "passive"))
      (node (ref "Rvinb") (pin "2") (pinfunction "2_2") (pintype "passive"))
      (node (ref "Rvint") (pin "1") (pinfunction "1_1") (pintype "passive"))
      (node (ref "U8") (pin "15") (pinfunction "AVIN_15") (pintype "input"))
    )
    (net (code "23") (name "/FBOUT") (class "Default")
      (node (ref "C59") (pin "2") (pinfunction "2_2") (pintype "passive"))
      (node (ref "Rvoutb") (pin "2") (pinfunction "2_2") (pintype "passive"))
      (node (ref "Rvoutt") (pin "1") (pinfunction "1_1") (pintype "passive"))
      (node (ref "U8") (pin "17") (pinfunction "AVOUT_17") (pintype "output"))
    )
    (net (code "24") (name "/HIA") (class "Default")
      (node (ref "Rsu2") (pin "2") (pinfunction "2_2") (pintype "passive"))
      (node (ref "U8") (pin "26") (pinfunction "HIA_26") (pintype "output"))
      (node (ref "Ugd") (pin "7") (pinfunction "HIA_7") (pintype "input"))
    )
    (net (code "25") (name "/HIB") (class "Default")
      (node (ref "Dsu1") (pin "2") (pinfunction "A_2") (pintype "passive"))
      (node (ref "Rsu3") (pin "2") (pinfunction "2_2") (pintype "passive"))
      (node (ref "U8") (pin "25") (pinfunction "HIB_25") (pintype "output"))
      (node (ref "Ugd") (pin "8") (pinfunction "HIB_8") (pintype "input"))
    )
    (net (code "26") (name "/IIN") (class "Default")
      (node (ref "Ciin") (pin "2") (pinfunction "2_2") (pintype "passive"))
      (node (ref "Riin") (pin "2") (pinfunction "2_2") (pintype "passive"))
      (node (ref "Ugd") (pin "3") (pinfunction "IIN_3") (pintype "output"))
    )
    (net (code "27") (name "/IOUT") (class "Default")
      (node (ref "Ciout") (pin "2") (pinfunction "2_2") (pintype "passive"))
      (node (ref "Riout") (pin "2") (pinfunction "2_2") (pintype "passive"))
      (node (ref "Ugd") (pin "12") (pinfunction "IOUT_12") (pintype "output"))
    )
    (net (code "28") (name "/LED_A") (class "Default")
      (node (ref "J1") (pin "11") (pinfunction "11_11") (pintype "passive"))
      (node (ref "J2") (pin "9") (pinfunction "9_9") (pintype "passive"))
      (node (ref "R_LEDB_O") (pin "2") (pinfunction "2_2") (pintype "passive"))
    )
    (net (code "29") (name "/LED_B") (class "Default")
      (node (ref "J1") (pin "9") (pinfunction "9_9") (pintype "passive"))
      (node (ref "J2") (pin "11") (pinfunction "11_11") (pintype "passive"))
      (node (ref "R_LEDA_O") (pin "2") (pinfunction "2_2") (pintype "passive"))
    )
    (net (code "30") (name "/LED_VSS") (class "Default")
      (node (ref "Q_LEDA") (pin "2") (pinfunction "S_2") (pintype "passive"))
      (node (ref "Q_LEDB") (pin "2") (pinfunction "S_2") (pintype "passive"))
      (node (ref "Q_LEDVSS") (pin "3") (pinfunction "D_3") (pintype "passive"))
    )
    (net (code "31") (name "/LIA") (class "Default")
      (node (ref "U8") (pin "27") (pinfunction "LIA_27") (pintype "output"))
      (node (ref "Ugd") (pin "6") (pinfunction "LIA_6") (pintype "input"))
    )
    (net (code "32") (name "/LIB") (class "Default")
      (node (ref "U8") (pin "24") (pinfunction "LIB_24") (pintype "output"))
      (node (ref "Ugd") (pin "9") (pinfunction "LIB_9") (pintype "input"))
    )
    (net (code "33") (name "/NC4") (class "Default")
      (node (ref "C69") (pin "2") (pinfunction "2_2") (pintype "passive"))
      (node (ref "Rnc4") (pin "1") (pinfunction "1_1") (pintype "passive"))
      (node (ref "U8") (pin "23") (pinfunction "NC4_23") (pintype "passive"))
    )
    (net (code "34") (name "/OVS") (class "Default")
      (node (ref "Rovs") (pin "1") (pinfunction "1_1") (pintype "passive"))
      (node (ref "Ugd") (pin "16") (pinfunction "OVS_16") (pintype "passive"))
    )
    (net (code "35") (name "/PAN_DET") (class "Default")
      (node (ref "D_1A") (pin "1") (pinfunction "K_1") (pintype "passive"))
      (node (ref "D_1B") (pin "1") (pinfunction "K_1") (pintype "passive"))
      (node (ref "Q_LEDVSS") (pin "1") (pinfunction "G_1") (pintype "passive"))
    )
    (net (code "36") (name "/PM") (class "Default")
      (node (ref "Rpm") (pin "2") (pinfunction "2_2") (pintype "passive"))
      (node (ref "U8") (pin "28") (pinfunction "PM_28") (pintype "input"))
    )
    (net (code "37") (name "/PM_OUT") (class "Default")
      (node (ref "U8") (pin "11") (pinfunction "PM_OUT_11") (pintype "output"))
    )
    (net (code "38") (name "/POLARITY") (class "Default")
      (node (ref "Q_LEDA") (pin "3") (pinfunction "D_3") (pintype "passive"))
      (node (ref "Q_LEDB") (pin "1") (pinfunction "G_1") (pintype "passive"))
      (node (ref "R_LEDB_O") (pin "1") (pinfunction "1_1") (pintype "passive"))
    )
    (net (code "39") (name "/RESIN") (class "Default")
      (node (ref "Rrst") (pin "1") (pinfunction "1_1") (pintype "passive"))
      (node (ref "SWrst") (pin "1") (pinfunction "1_1") (pintype "passive"))
      (node (ref "Urst") (pin "2") (pinfunction "~{RESIN}_2") (pintype "input"))
    )
    (net (code "40") (name "/SIA") (class "Default")
      (node (ref "Riinsns1") (pin "1") (pinfunction "1_1") (pintype "passive"))
      (node (ref "Ugd") (pin "1") (pinfunction "SIA_1") (pintype "input"))
    )
    (net (code "41") (name "/SIB") (class "Default")
      (node (ref "Rioutsns1") (pin "1") (pinfunction "1_1") (pintype "passive"))
      (node (ref "Ugd") (pin "14") (pinfunction "SIB_14") (pintype "input"))
    )
    (net (code "42") (name "/SOA") (class "Default")
      (node (ref "Riinsns2") (pin "1") (pinfunction "1_1") (pintype "passive"))
      (node (ref "Ugd") (pin "2") (pinfunction "SDA_2") (pintype "input"))
    )
    (net (code "43") (name "/SOB") (class "Default")
      (node (ref "Rioutsns2") (pin "1") (pinfunction "1_1") (pintype "passive"))
      (node (ref "Ugd") (pin "13") (pinfunction "SOB_13") (pintype "output"))
    )
    (net (code "44") (name "/SOL_1A") (class "Default")
      (node (ref "D1_a") (pin "2") (pinfunction "A_2") (pintype "passive"))
      (node (ref "D1_b") (pin "2") (pinfunction "A_2") (pintype "passive"))
      (node (ref "D1_c") (pin "2") (pinfunction "A_2") (pintype "passive"))
      (node (ref "D1_d") (pin "2") (pinfunction "A_2") (pintype "passive"))
      (node (ref "D1_e") (pin "2") (pinfunction "A_2") (pintype "passive"))
      (node (ref "D1_f") (pin "2") (pinfunction "A_2") (pintype "passive"))
      (node (ref "D3_a") (pin "1") (pinfunction "K_1") (pintype "passive"))
      (node (ref "D3_b") (pin "1") (pinfunction "K_1") (pintype "passive"))
      (node (ref "D3_c") (pin "1") (pinfunction "K_1") (pintype "passive"))
      (node (ref "D3_d") (pin "1") (pinfunction "K_1") (pintype "passive"))
      (node (ref "D3_e") (pin "1") (pinfunction "K_1") (pintype "passive"))
      (node (ref "D3_f") (pin "1") (pinfunction "K_1") (pintype "passive"))
      (node (ref "J1") (pin "1") (pinfunction "1_1") (pintype "passive"))
      (node (ref "J1") (pin "2") (pinfunction "2_2") (pintype "passive"))
      (node (ref "J1") (pin "3") (pinfunction "3_3") (pintype "passive"))
      (node (ref "J1") (pin "4") (pinfunction "4_4") (pintype "passive"))
      (node (ref "J1") (pin "5") (pinfunction "5_5") (pintype "passive"))
      (node (ref "J1") (pin "6") (pinfunction "6_6") (pintype "passive"))
      (node (ref "J1") (pin "7") (pinfunction "7_7") (pintype "passive"))
      (node (ref "J1") (pin "8") (pinfunction "8_8") (pintype "passive"))
      (node (ref "R_1A_a") (pin "1") (pinfunction "1_1") (pintype "passive"))
    )
    (net (code "45") (name "/SOL_1B") (class "Default")
      (node (ref "D2_a") (pin "2") (pinfunction "A_2") (pintype "passive"))
      (node (ref "D2_b") (pin "2") (pinfunction "A_2") (pintype "passive"))
      (node (ref "D2_c") (pin "2") (pinfunction "A_2") (pintype "passive"))
      (node (ref "D2_d") (pin "2") (pinfunction "A_2") (pintype "passive"))
      (node (ref "D2_e") (pin "2") (pinfunction "A_2") (pintype "passive"))
      (node (ref "D2_f") (pin "2") (pinfunction "A_2") (pintype "passive"))
      (node (ref "D4_a") (pin "1") (pinfunction "K_1") (pintype "passive"))
      (node (ref "D4_b") (pin "1") (pinfunction "K_1") (pintype "passive"))
      (node (ref "D4_c") (pin "1") (pinfunction "K_1") (pintype "passive"))
      (node (ref "D4_d") (pin "1") (pinfunction "K_1") (pintype "passive"))
      (node (ref "D4_e") (pin "1") (pinfunction "K_1") (pintype "passive"))
      (node (ref "D4_f") (pin "1") (pinfunction "K_1") (pintype "passive"))
      (node (ref "J2") (pin "1") (pinfunction "1_1") (pintype "passive"))
      (node (ref "J2") (pin "2") (pinfunction "2_2") (pintype "passive"))
      (node (ref "J2") (pin "3") (pinfunction "3_3") (pintype "passive"))
      (node (ref "J2") (pin "4") (pinfunction "4_4") (pintype "passive"))
      (node (ref "J2") (pin "5") (pinfunction "5_5") (pintype "passive"))
      (node (ref "J2") (pin "6") (pinfunction "6_6") (pintype "passive"))
      (node (ref "J2") (pin "7") (pinfunction "7_7") (pintype "passive"))
      (node (ref "J2") (pin "8") (pinfunction "8_8") (pintype "passive"))
      (node (ref "R_1B_a") (pin "1") (pinfunction "1_1") (pintype "passive"))
    )
    (net (code "46") (name "/SW1") (class "Default")
      (node (ref "C18") (pin "2") (pinfunction "2_2") (pintype "passive"))
      (node (ref "Cboot1") (pin "1") (pinfunction "1_1") (pintype "passive"))
      (node (ref "Dbg1") (pin "1") (pinfunction "K_1") (pintype "passive"))
      (node (ref "Dtg1") (pin "2") (pinfunction "A_2") (pintype "passive"))
      (node (ref "L1") (pin "1") (pinfunction "1_1") (pintype "passive"))
      (node (ref "L10") (pin "1") (pinfunction "1_1") (pintype "passive"))
      (node (ref "L11") (pin "1") (pinfunction "1_1") (pintype "passive"))
      (node (ref "L12") (pin "1") (pinfunction "1_1") (pintype "passive"))
      (node (ref "L2") (pin "1") (pinfunction "1_1") (pintype "passive"))
      (node (ref "L3") (pin "1") (pinfunction "1_1") (pintype "passive"))
      (node (ref "L4") (pin "1") (pinfunction "1_1") (pintype "passive"))
      (node (ref "L5") (pin "1") (pinfunction "1_1") (pintype "passive"))
      (node (ref "L6") (pin "1") (pinfunction "1_1") (pintype "passive"))
      (node (ref "L7") (pin "1") (pinfunction "1_1") (pintype "passive"))
      (node (ref "L8") (pin "1") (pinfunction "1_1") (pintype "passive"))
      (node (ref "L9") (pin "1") (pinfunction "1_1") (pintype "passive"))
      (node (ref "Qbg1") (pin "2") (pinfunction "D_2") (pintype "passive"))
      (node (ref "Qtg1") (pin "3") (pinfunction "S_3") (pintype "passive"))
      (node (ref "Rtg1s") (pin "1") (pinfunction "1_1") (pintype "passive"))
      (node (ref "Ugd") (pin "28") (pinfunction "HSA_28") (pintype "passive"))
    )
    (net (code "47") (name "/SW2") (class "Default")
      (node (ref "C19") (pin "2") (pinfunction "2_2") (pintype "passive"))
      (node (ref "Cboot2") (pin "1") (pinfunction "1_1") (pintype "passive"))
      (node (ref "Dbg2") (pin "1") (pinfunction "K_1") (pintype "passive"))
      (node (ref "Dtg2") (pin "2") (pinfunction "A_2") (pintype "passive"))
      (node (ref "L1") (pin "2") (pinfunction "2_2") (pintype "passive"))
      (node (ref "L10") (pin "2") (pinfunction "2_2") (pintype "passive"))
      (node (ref "L11") (pin "2") (pinfunction "2_2") (pintype "passive"))
      (node (ref "L12") (pin "2") (pinfunction "2_2") (pintype "passive"))
      (node (ref "L2") (pin "2") (pinfunction "2_2") (pintype "passive"))
      (node (ref "L3") (pin "2") (pinfunction "2_2") (pintype "passive"))
      (node (ref "L4") (pin "2") (pinfunction "2_2") (pintype "passive"))
      (node (ref "L5") (pin "2") (pinfunction "2_2") (pintype "passive"))
      (node (ref "L6") (pin "2") (pinfunction "2_2") (pintype "passive"))
      (node (ref "L7") (pin "2") (pinfunction "2_2") (pintype "passive"))
      (node (ref "L8") (pin "2") (pinfunction "2_2") (pintype "passive"))
      (node (ref "L9") (pin "2") (pinfunction "2_2") (pintype "passive"))
      (node (ref "Qbg2") (pin "2") (pinfunction "D_2") (pintype "passive"))
      (node (ref "Qtg2") (pin "3") (pinfunction "S_3") (pintype "passive"))
      (node (ref "Rtg2s") (pin "2") (pinfunction "2_2") (pintype "passive"))
      (node (ref "Ugd") (pin "18") (pinfunction "HSB_18") (pintype "passive"))
    )
    (net (code "48") (name "/TG1") (class "Default")
      (node (ref "D3") (pin "1") (pinfunction "K_1") (pintype "passive"))
      (node (ref "Rtg1a") (pin "1") (pinfunction "1_1") (pintype "passive"))
      (node (ref "Rtg1b") (pin "1") (pinfunction "1_1") (pintype "passive"))
      (node (ref "Ugd") (pin "27") (pinfunction "HOA_27") (pintype "output"))
    )
    (net (code "49") (name "/TG2") (class "Default")
      (node (ref "D4") (pin "1") (pinfunction "K_1") (pintype "passive"))
      (node (ref "Rtg2a") (pin "2") (pinfunction "2_2") (pintype "passive"))
      (node (ref "Rtg2b") (pin "2") (pinfunction "2_2") (pintype "passive"))
      (node (ref "Ugd") (pin "19") (pinfunction "HOB_19") (pintype "output"))
    )
    (net (code "50") (name "/nRST") (class "Default")
      (node (ref "C66") (pin "2") (pinfunction "2_2") (pintype "passive"))
      (node (ref "R26") (pin "1") (pinfunction "1_1") (pintype "passive"))
      (node (ref "U8") (pin "1") (pinfunction "RST_1") (pintype "input"))
      (node (ref "Ugd") (pin "10") (pinfunction "PGD_10") (pintype "open_collector"))
      (node (ref "Urst") (pin "5") (pinfunction "~{RESET}_5") (pintype "output"))
    )
    (net (code "51") (name "AGND") (class "Default")
      (node (ref "Ciin") (pin "1") (pinfunction "1_1") (pintype "passive"))
      (node (ref "Ciout") (pin "1") (pinfunction "1_1") (pintype "passive"))
      (node (ref "Ragnd") (pin "2") (pinfunction "2_2") (pintype "passive"))
      (node (ref "Riin") (pin "1") (pinfunction "1_1") (pintype "passive"))
      (node (ref "Riout") (pin "1") (pinfunction "1_1") (pintype "passive"))
      (node (ref "U8") (pin "13") (pinfunction "VSSA_13") (pintype "power_in"))
      (node (ref "Ugd") (pin "5") (pinfunction "AGND_5") (pintype "power_in"))
    )
    (net (code "52") (name "GND") (class "Default")
      (node (ref "C1") (pin "1") (pinfunction "1_1") (pintype "passive"))
      (node (ref "C10") (pin "1") (pinfunction "1_1") (pintype "passive"))
      (node (ref "C11") (pin "1") (pinfunction "1_1") (pintype "passive"))
      (node (ref "C12") (pin "1") (pinfunction "1_1") (pintype "passive"))
      (node (ref "C12v1") (pin "2") (pinfunction "2_2") (pintype "passive"))
      (node (ref "C12v10") (pin "2") (pinfunction "2_2") (pintype "passive"))
      (node (ref "C12v11") (pin "2") (pinfunction "2_2") (pintype "passive"))
      (node (ref "C12v12") (pin "2") (pinfunction "2_2") (pintype "passive"))
      (node (ref "C12v2") (pin "2") (pinfunction "2_2") (pintype "passive"))
      (node (ref "C12v3") (pin "2") (pinfunction "2_2") (pintype "passive"))
      (node (ref "C12v4") (pin "2") (pinfunction "2_2") (pintype "passive"))
      (node (ref "C12v5") (pin "2") (pinfunction "2_2") (pintype "passive"))
      (node (ref "C12v6") (pin "2") (pinfunction "2_2") (pintype "passive"))
      (node (ref "C12v7") (pin "2") (pinfunction "2_2") (pintype "passive"))
      (node (ref "C12v8") (pin "2") (pinfunction "2_2") (pintype "passive"))
      (node (ref "C12v9") (pin "2") (pinfunction "2_2") (pintype "passive"))
      (node (ref "C130") (pin "1") (pinfunction "1_1") (pintype "passive"))
      (node (ref "C14") (pin "2") (pinfunction "2_2") (pintype "passive"))
      (node (ref "C15") (pin "2") (pinfunction "2_2") (pintype "passive"))
      (node (ref "C16") (pin "1") (pinfunction "1_1") (pintype "passive"))
      (node (ref "C20") (pin "1") (pinfunction "1_1") (pintype "passive"))
      (node (ref "C201") (pin "2") (pinfunction "2_2") (pintype "passive"))
      (node (ref "C25") (pin "1") (pinfunction "1_1") (pintype "passive"))
      (node (ref "C27") (pin "1") (pinfunction "1_1") (pintype "passive"))
      (node (ref "C28") (pin "1") (pinfunction "1_1") (pintype "passive"))
      (node (ref "C29") (pin "1") (pinfunction "1_1") (pintype "passive"))
      (node (ref "C30") (pin "1") (pinfunction "1_1") (pintype "passive"))
      (node (ref "C33") (pin "2") (pinfunction "2_2") (pintype "passive"))
      (node (ref "C34") (pin "1") (pinfunction "1_1") (pintype "passive"))
      (node (ref "C36") (pin "1") (pinfunction "1_1") (pintype "passive"))
      (node (ref "C37") (pin "2") (pinfunction "2_2") (pintype "passive"))
      (node (ref "C39") (pin "1") (pinfunction "1_1") (pintype "passive"))
      (node (ref "C4") (pin "1") (pinfunction "1_1") (pintype "passive"))
      (node (ref "C41") (pin "1") (pinfunction "1_1") (pintype "passive"))
      (node (ref "C410") (pin "1") (pinfunction "1_1") (pintype "passive"))
      (node (ref "C44") (pin "1") (pinfunction "1_1") (pintype "passive"))
      (node (ref "C45") (pin "1") (pinfunction "1_1") (pintype "passive"))
      (node (ref "C450") (pin "1") (pinfunction "1_1") (pintype "passive"))
      (node (ref "C470") (pin "1") (pinfunction "1_1") (pintype "passive"))
      (node (ref "C49") (pin "1") (pinfunction "1_1") (pintype "passive"))
      (node (ref "C5") (pin "1") (pinfunction "1_1") (pintype "passive"))
      (node (ref "C50") (pin "1") (pinfunction "1_1") (pintype "passive"))
      (node (ref "C51") (pin "1") (pinfunction "1_1") (pintype "passive"))
      (node (ref "C52") (pin "2") (pinfunction "2_2") (pintype "passive"))
      (node (ref "C53") (pin "1") (pinfunction "1_1") (pintype "passive"))
      (node (ref "C54") (pin "1") (pinfunction "1_1") (pintype "passive"))
      (node (ref "C55") (pin "1") (pinfunction "1_1") (pintype "passive"))
      (node (ref "C58") (pin "1") (pinfunction "1_1") (pintype "passive"))
      (node (ref "C59") (pin "1") (pinfunction "1_1") (pintype "passive"))
      (node (ref "C5v1") (pin "1") (pinfunction "1_1") (pintype "passive"))
      (node (ref "C5v2") (pin "1") (pinfunction "1_1") (pintype "passive"))
      (node (ref "C6") (pin "1") (pinfunction "1_1") (pintype "passive"))
      (node (ref "C61") (pin "1") (pinfunction "1_1") (pintype "passive"))
      (node (ref "C620") (pin "1") (pinfunction "1_1") (pintype "passive"))
      (node (ref "C66") (pin "1") (pinfunction "1_1") (pintype "passive"))
      (node (ref "C69") (pin "1") (pinfunction "1_1") (pintype "passive"))
      (node (ref "C7") (pin "1") (pinfunction "1_1") (pintype "passive"))
      (node (ref "C70") (pin "1") (pinfunction "1_1") (pintype "passive"))
      (node (ref "C72") (pin "1") (pinfunction "1_1") (pintype "passive"))
      (node (ref "C8") (pin "1") (pinfunction "1_1") (pintype "passive"))
      (node (ref "C9") (pin "1") (pinfunction "1_1") (pintype "passive"))
      (node (ref "Cpsu1") (pin "1") (pinfunction "1_1") (pintype "passive"))
      (node (ref "Cref") (pin "1") (pinfunction "1_1") (pintype "passive"))
      (node (ref "Creset") (pin "1") (pinfunction "1_1") (pintype "passive"))
      (node (ref "Csu1") (pin "1") (pinfunction "1_1") (pintype "passive"))
      (node (ref "Csu2") (pin "1") (pinfunction "1_1") (pintype "passive"))
      (node (ref "Cvcc") (pin "1") (pinfunction "1_1") (pintype "passive"))
      (node (ref "Cvdd") (pin "1") (pinfunction "1_1") (pintype "passive"))
      (node (ref "D14") (pin "1") (pinfunction "K_1") (pintype "passive"))
      (node (ref "D15") (pin "1") (pinfunction "K_1") (pintype "passive"))
      (node (ref "D3_a") (pin "2") (pinfunction "A_2") (pintype "passive"))
      (node (ref "D3_b") (pin "2") (pinfunction "A_2") (pintype "passive"))
      (node (ref "D3_c") (pin "2") (pinfunction "A_2") (pintype "passive"))
      (node (ref "D3_d") (pin "2") (pinfunction "A_2") (pintype "passive"))
      (node (ref "D3_e") (pin "2") (pinfunction "A_2") (pintype "passive"))
      (node (ref "D3_f") (pin "2") (pinfunction "A_2") (pintype "passive"))
      (node (ref "D4_a") (pin "2") (pinfunction "A_2") (pintype "passive"))
      (node (ref "D4_b") (pin "2") (pinfunction "A_2") (pintype "passive"))
      (node (ref "D4_c") (pin "2") (pinfunction "A_2") (pintype "passive"))
      (node (ref "D4_d") (pin "2") (pinfunction "A_2") (pintype "passive"))
      (node (ref "D4_e") (pin "2") (pinfunction "A_2") (pintype "passive"))
      (node (ref "D4_f") (pin "2") (pinfunction "A_2") (pintype "passive"))
      (node (ref "D_1A_G") (pin "2") (pinfunction "A_2") (pintype "passive"))
      (node (ref "D_1B_G") (pin "2") (pinfunction "A_2") (pintype "passive"))
      (node (ref "D_CLAMP_18") (pin "2") (pinfunction "A_2") (pintype "passive"))
      (node (ref "Dpsu1") (pin "2") (pinfunction "A_2") (pintype "passive"))
      (node (ref "Jout") (pin "MINUS") (pinfunction "-_MINUS") (pintype "passive"))
      (node (ref "Q_LEDVSS") (pin "2") (pinfunction "S_2") (pintype "passive"))
      (node (ref "R110") (pin "1") (pinfunction "1_1") (pintype "passive"))
      (node (ref "R140") (pin "1") (pinfunction "1_1") (pintype "passive"))
      (node (ref "R38") (pin "1") (pinfunction "1_1") (pintype "passive"))
      (node (ref "R39") (pin "1") (pinfunction "1_1") (pintype "passive"))
      (node (ref "R40") (pin "1") (pinfunction "1_1") (pintype "passive"))
      (node (ref "R41") (pin "1") (pinfunction "1_1") (pintype "passive"))
      (node (ref "R_1A_c") (pin "1") (pinfunction "1_1") (pintype "passive"))
      (node (ref "R_1B_c") (pin "1") (pinfunction "1_1") (pintype "passive"))
      (node (ref "Ragnd") (pin "1") (pinfunction "1_1") (pintype "passive"))
      (node (ref "Rcl2") (pin "1") (pinfunction "1_1") (pintype "passive"))
      (node (ref "Rcs") (pin "2") (pinfunction "2_2") (pintype "passive"))
      (node (ref "Rcsg") (pin "2") (pinfunction "2_2") (pintype "passive"))
      (node (ref "Rovs") (pin "2") (pinfunction "2_2") (pintype "passive"))
      (node (ref "Rpsufb2") (pin "1") (pinfunction "1_1") (pintype "passive"))
      (node (ref "Rsu1") (pin "1") (pinfunction "1_1") (pintype "passive"))
      (node (ref "Rsu5") (pin "2") (pinfunction "2_2") (pintype "passive"))
      (node (ref "Rvinb") (pin "1") (pinfunction "1_1") (pintype "passive"))
      (node (ref "Rvoutb") (pin "1") (pinfunction "1_1") (pintype "passive"))
      (node (ref "SWrst") (pin "2") (pinfunction "2_2") (pintype "passive"))
      (node (ref "U5V2") (pin "2") (pinfunction "GND_2") (pintype "power_in"))
      (node (ref "U8") (pin "10") (pinfunction "NC3_10") (pintype "passive"))
      (node (ref "U8") (pin "2") (pinfunction "NC1_2") (pintype "passive"))
      (node (ref "U8") (pin "22") (pinfunction "I2C2_22") (pintype "bidirectional"))
      (node (ref "U8") (pin "4") (pinfunction "VSSD_4") (pintype "power_in"))
      (node (ref "U8") (pin "7") (pinfunction "I2C1_7") (pintype "bidirectional"))
      (node (ref "Ugd") (pin "23") (pinfunction "PGND_23") (pintype "power_in"))
      (node (ref "Upsu") (pin "4") (pinfunction "RTN_4") (pintype "bidirectional"))
      (node (ref "Urst") (pin "4") (pinfunction "GND_4") (pintype "power_in"))
    )
    (net (code "53") (name "Net-(D3-A)") (class "Default")
      (node (ref "D3") (pin "2") (pinfunction "A_2") (pintype "passive"))
      (node (ref "Qtg1") (pin "1") (pinfunction "G_1") (pintype "passive"))
      (node (ref "Rtg1a") (pin "2") (pinfunction "2_2") (pintype "passive"))
      (node (ref "Rtg1b") (pin "2") (pinfunction "2_2") (pintype "passive"))
      (node (ref "Rtg1s") (pin "2") (pinfunction "2_2") (pintype "passive"))
    )
    (net (code "54") (name "Net-(D4-A)") (class "Default")
      (node (ref "D4") (pin "2") (pinfunction "A_2") (pintype "passive"))
      (node (ref "Qtg2") (pin "1") (pinfunction "G_1") (pintype "passive"))
      (node (ref "Rtg2a") (pin "1") (pinfunction "1_1") (pintype "passive"))
      (node (ref "Rtg2b") (pin "1") (pinfunction "1_1") (pintype "passive"))
      (node (ref "Rtg2s") (pin "1") (pinfunction "1_1") (pintype "passive"))
    )
    (net (code "55") (name "Net-(D5-A)") (class "Default")
      (node (ref "D5") (pin "2") (pinfunction "A_2") (pintype "passive"))
      (node (ref "Qbg1") (pin "1") (pinfunction "G_1") (pintype "passive"))
      (node (ref "Rbg1a") (pin "2") (pinfunction "2_2") (pintype "passive"))
      (node (ref "Rbg1b") (pin "2") (pinfunction "2_2") (pintype "passive"))
      (node (ref "Rbg1s") (pin "2") (pinfunction "2_2") (pintype "passive"))
    )
    (net (code "56") (name "Net-(D6-A)") (class "Default")
      (node (ref "D6") (pin "2") (pinfunction "A_2") (pintype "passive"))
      (node (ref "Qbg2") (pin "1") (pinfunction "G_1") (pintype "passive"))
      (node (ref "Rbg2a") (pin "1") (pinfunction "1_1") (pintype "passive"))
      (node (ref "Rbg2b") (pin "1") (pinfunction "1_1") (pintype "passive"))
      (node (ref "Rbg2s") (pin "1") (pinfunction "1_1") (pintype "passive"))
    )
    (net (code "57") (name "Net-(D14-A)") (class "Default")
      (node (ref "C19") (pin "1") (pinfunction "1_1") (pintype "passive"))
      (node (ref "D14") (pin "2") (pinfunction "A_2") (pintype "passive"))
      (node (ref "R140") (pin "2") (pinfunction "2_2") (pintype "passive"))
    )
    (net (code "58") (name "Net-(D15-A)") (class "Default")
      (node (ref "C18") (pin "1") (pinfunction "1_1") (pintype "passive"))
      (node (ref "D15") (pin "2") (pinfunction "A_2") (pintype "passive"))
      (node (ref "R110") (pin "2") (pinfunction "2_2") (pintype "passive"))
    )
    (net (code "59") (name "Net-(D_CLAMP_1-A)") (class "Default")
      (node (ref "D_CLAMP_1") (pin "2") (pinfunction "A_2") (pintype "passive"))
      (node (ref "D_CLAMP_2") (pin "1") (pinfunction "K_1") (pintype "passive"))
    )
    (net (code "60") (name "Net-(D_CLAMP_2-A)") (class "Default")
      (node (ref "D_CLAMP_2") (pin "2") (pinfunction "A_2") (pintype "passive"))
      (node (ref "D_CLAMP_3") (pin "1") (pinfunction "K_1") (pintype "passive"))
    )
    (net (code "61") (name "Net-(D_CLAMP_3-A)") (class "Default")
      (node (ref "D_CLAMP_3") (pin "2") (pinfunction "A_2") (pintype "passive"))
      (node (ref "D_CLAMP_4") (pin "1") (pinfunction "K_1") (pintype "passive"))
    )
    (net (code "62") (name "Net-(D_CLAMP_4-A)") (class "Default")
      (node (ref "D_CLAMP_4") (pin "2") (pinfunction "A_2") (pintype "passive"))
      (node (ref "D_CLAMP_5") (pin "1") (pinfunction "K_1") (pintype "passive"))
    )
    (net (code "63") (name "Net-(D_CLAMP_5-A)") (class "Default")
      (node (ref "D_CLAMP_5") (pin "2") (pinfunction "A_2") (pintype "passive"))
      (node (ref "D_CLAMP_6") (pin "1") (pinfunction "K_1") (pintype "passive"))
    )
    (net (code "64") (name "Net-(D_CLAMP_6-A)") (class "Default")
      (node (ref "D_CLAMP_6") (pin "2") (pinfunction "A_2") (pintype "passive"))
      (node (ref "D_CLAMP_7") (pin "1") (pinfunction "K_1") (pintype "passive"))
    )
    (net (code "65") (name "Net-(D_CLAMP_7-A)") (class "Default")
      (node (ref "D_CLAMP_7") (pin "2") (pinfunction "A_2") (pintype "passive"))
      (node (ref "D_CLAMP_8") (pin "1") (pinfunction "K_1") (pintype "passive"))
    )
    (net (code "66") (name "Net-(D_CLAMP_10-K)") (class "Default")
      (node (ref "D_CLAMP_10") (pin "1") (pinfunction "K_1") (pintype "passive"))
      (node (ref "D_CLAMP_9") (pin "2") (pinfunction "A_2") (pintype "passive"))
    )
    (net (code "67") (name "Net-(D_CLAMP_11-A)") (class "Default")
      (node (ref "D_CLAMP_11") (pin "2") (pinfunction "A_2") (pintype "passive"))
      (node (ref "D_CLAMP_12") (pin "1") (pinfunction "K_1") (pintype "passive"))
    )
    (net (code "68") (name "Net-(D_CLAMP_12-A)") (class "Default")
      (node (ref "D_CLAMP_12") (pin "2") (pinfunction "A_2") (pintype "passive"))
      (node (ref "D_CLAMP_13") (pin "1") (pinfunction "K_1") (pintype "passive"))
    )
    (net (code "69") (name "Net-(D_CLAMP_13-A)") (class "Default")
      (node (ref "D_CLAMP_13") (pin "2") (pinfunction "A_2") (pintype "passive"))
      (node (ref "D_CLAMP_14") (pin "1") (pinfunction "K_1") (pintype "passive"))
    )
    (net (code "70") (name "Net-(D_CLAMP_14-A)") (class "Default")
      (node (ref "D_CLAMP_14") (pin "2") (pinfunction "A_2") (pintype "passive"))
      (node (ref "D_CLAMP_15") (pin "1") (pinfunction "K_1") (pintype "passive"))
    )
    (net (code "71") (name "Net-(D_CLAMP_15-A)") (class "Default")
      (node (ref "D_CLAMP_15") (pin "2") (pinfunction "A_2") (pintype "passive"))
      (node (ref "D_CLAMP_16") (pin "1") (pinfunction "K_1") (pintype "passive"))
    )
    (net (code "72") (name "Net-(D_CLAMP_16-A)") (class "Default")
      (node (ref "D_CLAMP_16") (pin "2") (pinfunction "A_2") (pintype "passive"))
      (node (ref "D_CLAMP_17") (pin "1") (pinfunction "K_1") (pintype "passive"))
    )
    (net (code "73") (name "Net-(D_CLAMP_17-A)") (class "Default")
      (node (ref "D_CLAMP_17") (pin "2") (pinfunction "A_2") (pintype "passive"))
      (node (ref "D_CLAMP_18") (pin "1") (pinfunction "K_1") (pintype "passive"))
    )
    (net (code "74") (name "Net-(Dpsu1-K)") (class "Default")
      (node (ref "Cbst") (pin "2") (pinfunction "2_2") (pintype "passive"))
      (node (ref "Dpsu1") (pin "1") (pinfunction "K_1") (pintype "passive"))
      (node (ref "L200") (pin "1") (pinfunction "1_1") (pintype "passive"))
      (node (ref "Upsu") (pin "1") (pinfunction "SW_1") (pintype "bidirectional"))
    )
    (net (code "75") (name "Net-(J1-Pad10)") (class "Default")
      (node (ref "J1") (pin "10") (pinfunction "10_10") (pintype "passive"))
      (node (ref "R101") (pin "2") (pinfunction "2_2") (pintype "passive"))
    )
    (net (code "76") (name "Net-(J1-Pad12)") (class "Default")
      (node (ref "J1") (pin "12") (pinfunction "12_12") (pintype "passive"))
      (node (ref "R100") (pin "2") (pinfunction "2_2") (pintype "passive"))
    )
    (net (code "77") (name "Net-(J1-SHIELD-PadS1)") (class "Default")
      (node (ref "J1") (pin "S1") (pinfunction "SHIELD_S1") (pintype "passive"))
      (node (ref "J1") (pin "S2") (pinfunction "SHIELD_S2") (pintype "passive"))
    )
    (net (code "78") (name "Net-(J2-Pad10)") (class "Default")
      (node (ref "J2") (pin "10") (pinfunction "10_10") (pintype "passive"))
      (node (ref "R102") (pin "2") (pinfunction "2_2") (pintype "passive"))
    )
    (net (code "79") (name "Net-(J2-Pad12)") (class "Default")
      (node (ref "J2") (pin "12") (pinfunction "12_12") (pintype "passive"))
      (node (ref "R103") (pin "2") (pinfunction "2_2") (pintype "passive"))
    )
    (net (code "80") (name "Net-(J2-SHIELD-PadS1)") (class "Default")
      (node (ref "J2") (pin "S1") (pinfunction "SHIELD_S1") (pintype "passive"))
      (node (ref "J2") (pin "S2") (pinfunction "SHIELD_S2") (pintype "passive"))
    )
    (net (code "81") (name "Net-(Q_LEDB-D)") (class "Default")
      (node (ref "Q_LEDB") (pin "3") (pinfunction "D_3") (pintype "passive"))
      (node (ref "R_LEDA_O") (pin "1") (pinfunction "1_1") (pintype "passive"))
    )
    (net (code "82") (name "Net-(Qsu-B)") (class "Default")
      (node (ref "Csu1") (pin "2") (pinfunction "2_2") (pintype "passive"))
      (node (ref "Qsu") (pin "1") (pinfunction "B_1") (pintype "passive"))
      (node (ref "Rsu2") (pin "1") (pinfunction "1_1") (pintype "passive"))
      (node (ref "Rsu3") (pin "1") (pinfunction "1_1") (pintype "passive"))
      (node (ref "Rsu4") (pin "1") (pinfunction "1_1") (pintype "passive"))
    )
    (net (code "83") (name "Net-(R_1A_a-Pad2)") (class "Default")
      (node (ref "R_1A_a") (pin "2") (pinfunction "2_2") (pintype "passive"))
      (node (ref "R_1A_b") (pin "1") (pinfunction "1_1") (pintype "passive"))
    )
    (net (code "84") (name "Net-(R_1B_a-Pad2)") (class "Default")
      (node (ref "R_1B_a") (pin "2") (pinfunction "2_2") (pintype "passive"))
      (node (ref "R_1B_b") (pin "1") (pinfunction "1_1") (pintype "passive"))
    )
    (net (code "85") (name "Net-(Rcl1-Pad1)") (class "Default")
      (node (ref "Rcl1") (pin "1") (pinfunction "1_1") (pintype "passive"))
      (node (ref "Rcl2") (pin "2") (pinfunction "2_2") (pintype "passive"))
    )
    (net (code "86") (name "Net-(Ron-Pad1)") (class "Default")
      (node (ref "Ron") (pin "1") (pinfunction "1_1") (pintype "passive"))
      (node (ref "Ron_c") (pin "2") (pinfunction "2_2") (pintype "passive"))
    )
    (net (code "87") (name "Net-(U8-A0)") (class "Default")
      (node (ref "C49") (pin "2") (pinfunction "2_2") (pintype "passive"))
      (node (ref "R28") (pin "1") (pinfunction "1_1") (pintype "passive"))
      (node (ref "R38") (pin "2") (pinfunction "2_2") (pintype "passive"))
      (node (ref "U8") (pin "14") (pinfunction "A0_14") (pintype "bidirectional"))
    )
    (net (code "88") (name "Net-(U8-A2)") (class "Default")
      (node (ref "C50") (pin "2") (pinfunction "2_2") (pintype "passive"))
      (node (ref "R29") (pin "1") (pinfunction "1_1") (pintype "passive"))
      (node (ref "R39") (pin "2") (pinfunction "2_2") (pintype "passive"))
      (node (ref "U8") (pin "16") (pinfunction "A2_16") (pintype "bidirectional"))
    )
    (net (code "89") (name "Net-(U8-A4)") (class "Default")
      (node (ref "C51") (pin "2") (pinfunction "2_2") (pintype "passive"))
      (node (ref "R30") (pin "2") (pinfunction "2_2") (pintype "passive"))
      (node (ref "R40") (pin "2") (pinfunction "2_2") (pintype "passive"))
      (node (ref "U8") (pin "18") (pinfunction "A4_18") (pintype "bidirectional"))
    )
    (net (code "90") (name "Net-(U8-A6)") (class "Default")
      (node (ref "C52") (pin "1") (pinfunction "1_1") (pintype "passive"))
      (node (ref "R31") (pin "1") (pinfunction "1_1") (pintype "passive"))
      (node (ref "R41") (pin "2") (pinfunction "2_2") (pintype "passive"))
      (node (ref "U8") (pin "20") (pinfunction "A6_20") (pintype "bidirectional"))
    )
    (net (code "91") (name "Net-(U8-NC2)") (class "Default")
      (node (ref "R45") (pin "2") (pinfunction "2_2") (pintype "passive"))
      (node (ref "U8") (pin "5") (pinfunction "NC2_5") (pintype "passive"))
    )
    (net (code "92") (name "Net-(U8-VDDA)") (class "Default")
      (node (ref "C33") (pin "1") (pinfunction "1_1") (pintype "passive"))
      (node (ref "C39") (pin "2") (pinfunction "2_2") (pintype "passive"))
      (node (ref "R21") (pin "1") (pinfunction "1_1") (pintype "passive"))
      (node (ref "U8") (pin "12") (pinfunction "VDDA_12") (pintype "power_in"))
    )
    (net (code "93") (name "Net-(Upsu-BST)") (class "Default")
      (node (ref "Cbst") (pin "1") (pinfunction "1_1") (pintype "passive"))
      (node (ref "Upsu") (pin "2") (pinfunction "BST_2") (pintype "bidirectional"))
    )
    (net (code "94") (name "Net-(Upsu-FB)") (class "Default")
      (node (ref "Ccmp") (pin "1") (pinfunction "1_1") (pintype "passive"))
      (node (ref "Rpsufb1") (pin "2") (pinfunction "2_2") (pintype "passive"))
      (node (ref "Rpsufb2") (pin "2") (pinfunction "2_2") (pintype "passive"))
      (node (ref "Upsu") (pin "5") (pinfunction "FB_5") (pintype "bidirectional"))
    )
    (net (code "95") (name "Net-(Upsu-RCL)") (class "Default")
      (node (ref "Rcl1") (pin "2") (pinfunction "2_2") (pintype "passive"))
      (node (ref "Upsu") (pin "3") (pinfunction "RCL_3") (pintype "input"))
    )
    (net (code "96") (name "Net-(Upsu-RT{slash}SD)") (class "Default")
      (node (ref "Ron") (pin "2") (pinfunction "2_2") (pintype "passive"))
      (node (ref "Upsu") (pin "6") (pinfunction "RT/SD_6") (pintype "input"))
    )
    (net (code "97") (name "Net-(Upsu-VCC)") (class "Default")
      (node (ref "C201") (pin "1") (pinfunction "1_1") (pintype "passive"))
      (node (ref "Upsu") (pin "7") (pinfunction "VCC_7") (pintype "power_in"))
    )
    (net (code "98") (name "Net-(Upsu-VIN)") (class "Default")
      (node (ref "Cpsu1") (pin "2") (pinfunction "2_2") (pintype "passive"))
      (node (ref "Ron_c") (pin "1") (pinfunction "1_1") (pintype "passive"))
      (node (ref "Rpsu1") (pin "1") (pinfunction "1_1") (pintype "passive"))
      (node (ref "Rpsu2") (pin "1") (pinfunction "1_1") (pintype "passive"))
      (node (ref "Upsu") (pin "8") (pinfunction "VIN_8") (pintype "input"))
    )
    (net (code "99") (name "Net-(Urst-CT)") (class "Default")
      (node (ref "Creset") (pin "2") (pinfunction "2_2") (pintype "passive"))
      (node (ref "Urst") (pin "3") (pinfunction "CT_3") (pintype "input"))
    )
    (net (code "100") (name "Net-(Urst-REF)") (class "Default")
      (node (ref "Cref") (pin "2") (pinfunction "2_2") (pintype "passive"))
      (node (ref "Urst") (pin "1") (pinfunction "REF_1") (pintype "output"))
    )
    (net (code "101") (name "PGND") (class "Default")
      (node (ref "Dbg1") (pin "2") (pinfunction "A_2") (pintype "passive"))
      (node (ref "Dbg2") (pin "2") (pinfunction "A_2") (pintype "passive"))
      (node (ref "Qbg1") (pin "3") (pinfunction "S_3") (pintype "passive"))
      (node (ref "Qbg2") (pin "3") (pinfunction "S_3") (pintype "passive"))
      (node (ref "Rbg1s") (pin "1") (pinfunction "1_1") (pintype "passive"))
      (node (ref "Rbg2s") (pin "2") (pinfunction "2_2") (pintype "passive"))
      (node (ref "Rcs") (pin "1") (pinfunction "1_1") (pintype "passive"))
      (node (ref "Rcsp") (pin "2") (pinfunction "2_2") (pintype "passive"))
    )
    (net (code "102") (name "VCC_3V3") (class "Default")
      (node (ref "Qscl") (pin "1") (pinfunction "G_1") (pintype "passive"))
      (node (ref "Qsda") (pin "1") (pinfunction "G_1") (pintype "passive"))
      (node (ref "Rscl") (pin "2") (pinfunction "2_2") (pintype "passive"))
      (node (ref "Rsda") (pin "2") (pinfunction "2_2") (pintype "passive"))
    )
    (net (code "103") (name "VIN_N") (class "Default")
      (node (ref "C10") (pin "2") (pinfunction "2_2") (pintype "passive"))
      (node (ref "C11") (pin "2") (pinfunction "2_2") (pintype "passive"))
      (node (ref "C12") (pin "2") (pinfunction "2_2") (pintype "passive"))
      (node (ref "C130") (pin "2") (pinfunction "2_2") (pintype "passive"))
      (node (ref "C4") (pin "2") (pinfunction "2_2") (pintype "passive"))
      (node (ref "C5") (pin "2") (pinfunction "2_2") (pintype "passive"))
      (node (ref "C6") (pin "2") (pinfunction "2_2") (pintype "passive"))
      (node (ref "C7") (pin "2") (pinfunction "2_2") (pintype "passive"))
      (node (ref "C70") (pin "2") (pinfunction "2_2") (pintype "passive"))
      (node (ref "C72") (pin "2") (pinfunction "2_2") (pintype "passive"))
      (node (ref "C8") (pin "2") (pinfunction "2_2") (pintype "passive"))
      (node (ref "C9") (pin "2") (pinfunction "2_2") (pintype "passive"))
      (node (ref "Dtg1") (pin "1") (pinfunction "K_1") (pintype "passive"))
      (node (ref "Qtg1") (pin "2") (pinfunction "D_2") (pintype "passive"))
      (node (ref "R1") (pin "1") (pinfunction "1_1") (pintype "passive"))
      (node (ref "Riinsns2") (pin "2") (pinfunction "2_2") (pintype "passive"))
    )
    (net (code "104") (name "VIN_P") (class "Default")
      (node (ref "C41") (pin "2") (pinfunction "2_2") (pintype "passive"))
      (node (ref "C45") (pin "2") (pinfunction "2_2") (pintype "passive"))
      (node (ref "C53") (pin "2") (pinfunction "2_2") (pintype "passive"))
      (node (ref "C620") (pin "2") (pinfunction "2_2") (pintype "passive"))
      (node (ref "D1_a") (pin "1") (pinfunction "K_1") (pintype "passive"))
      (node (ref "D1_b") (pin "1") (pinfunction "K_1") (pintype "passive"))
      (node (ref "D1_c") (pin "1") (pinfunction "K_1") (pintype "passive"))
      (node (ref "D1_d") (pin "1") (pinfunction "K_1") (pintype "passive"))
      (node (ref "D1_e") (pin "1") (pinfunction "K_1") (pintype "passive"))
      (node (ref "D1_f") (pin "1") (pinfunction "K_1") (pintype "passive"))
      (node (ref "D2_a") (pin "1") (pinfunction "K_1") (pintype "passive"))
      (node (ref "D2_b") (pin "1") (pinfunction "K_1") (pintype "passive"))
      (node (ref "D2_c") (pin "1") (pinfunction "K_1") (pintype "passive"))
      (node (ref "D2_d") (pin "1") (pinfunction "K_1") (pintype "passive"))
      (node (ref "D2_e") (pin "1") (pinfunction "K_1") (pintype "passive"))
      (node (ref "D2_f") (pin "1") (pinfunction "K_1") (pintype "passive"))
      (node (ref "D_CLAMP_1") (pin "1") (pinfunction "K_1") (pintype "passive"))
      (node (ref "R1") (pin "2") (pinfunction "2_2") (pintype "passive"))
      (node (ref "Riinsns1") (pin "2") (pinfunction "2_2") (pintype "passive"))
      (node (ref "Rpsu1") (pin "2") (pinfunction "2_2") (pintype "passive"))
      (node (ref "Rvint") (pin "2") (pinfunction "2_2") (pintype "passive"))
    )
    (net (code "105") (name "VOUT_N") (class "Default")
      (node (ref "C54") (pin "2") (pinfunction "2_2") (pintype "passive"))
      (node (ref "C55") (pin "2") (pinfunction "2_2") (pintype "passive"))
      (node (ref "C58") (pin "2") (pinfunction "2_2") (pintype "passive"))
      (node (ref "C61") (pin "2") (pinfunction "2_2") (pintype "passive"))
      (node (ref "Jout") (pin "PLUS") (pinfunction "+_PLUS") (pintype "passive"))
      (node (ref "R10") (pin "2") (pinfunction "2_2") (pintype "passive"))
      (node (ref "Rioutsns2") (pin "2") (pinfunction "2_2") (pintype "passive"))
      (node (ref "Rpsu2") (pin "2") (pinfunction "2_2") (pintype "passive"))
      (node (ref "Rvoutt") (pin "2") (pinfunction "2_2") (pintype "passive"))
    )
    (net (code "106") (name "VOUT_P") (class "Default")
      (node (ref "C1") (pin "2") (pinfunction "2_2") (pintype "passive"))
      (node (ref "C16") (pin "2") (pinfunction "2_2") (pintype "passive"))
      (node (ref "C20") (pin "2") (pinfunction "2_2") (pintype "passive"))
      (node (ref "C25") (pin "2") (pinfunction "2_2") (pintype "passive"))
      (node (ref "C27") (pin "2") (pinfunction "2_2") (pintype "passive"))
      (node (ref "C28") (pin "2") (pinfunction "2_2") (pintype "passive"))
      (node (ref "C30") (pin "2") (pinfunction "2_2") (pintype "passive"))
      (node (ref "C36") (pin "2") (pinfunction "2_2") (pintype "passive"))
      (node (ref "C410") (pin "2") (pinfunction "2_2") (pintype "passive"))
      (node (ref "C44") (pin "2") (pinfunction "2_2") (pintype "passive"))
      (node (ref "C450") (pin "2") (pinfunction "2_2") (pintype "passive"))
      (node (ref "C470") (pin "2") (pinfunction "2_2") (pintype "passive"))
      (node (ref "Dtg2") (pin "1") (pinfunction "K_1") (pintype "passive"))
      (node (ref "Qtg2") (pin "2") (pinfunction "D_2") (pintype "passive"))
      (node (ref "R10") (pin "1") (pinfunction "1_1") (pintype "passive"))
      (node (ref "Rioutsns1") (pin "2") (pinfunction "2_2") (pintype "passive"))
    )
    (net (code "107") (name "unconnected-(Jout-PadM)") (class "Default")
      (node (ref "Jout") (pin "M") (pinfunction "M_M") (pintype "passive"))
    )
    (net (code "108") (name "unconnected-(Ugd-OVP-Pad15)") (class "Default")
      (node (ref "Ugd") (pin "15") (pinfunction "OVP_15") (pintype "passive"))
    )
    (net (code "109") (name "unconnected-(Urst-RESET-Pad6)") (class "Default")
      (node (ref "Urst") (pin "6") (pinfunction "RESET_6") (pintype "output"))
    )
  )
)
